# PKG900000001454.net
KiCad netlist of a schematic drawn in EAGLE
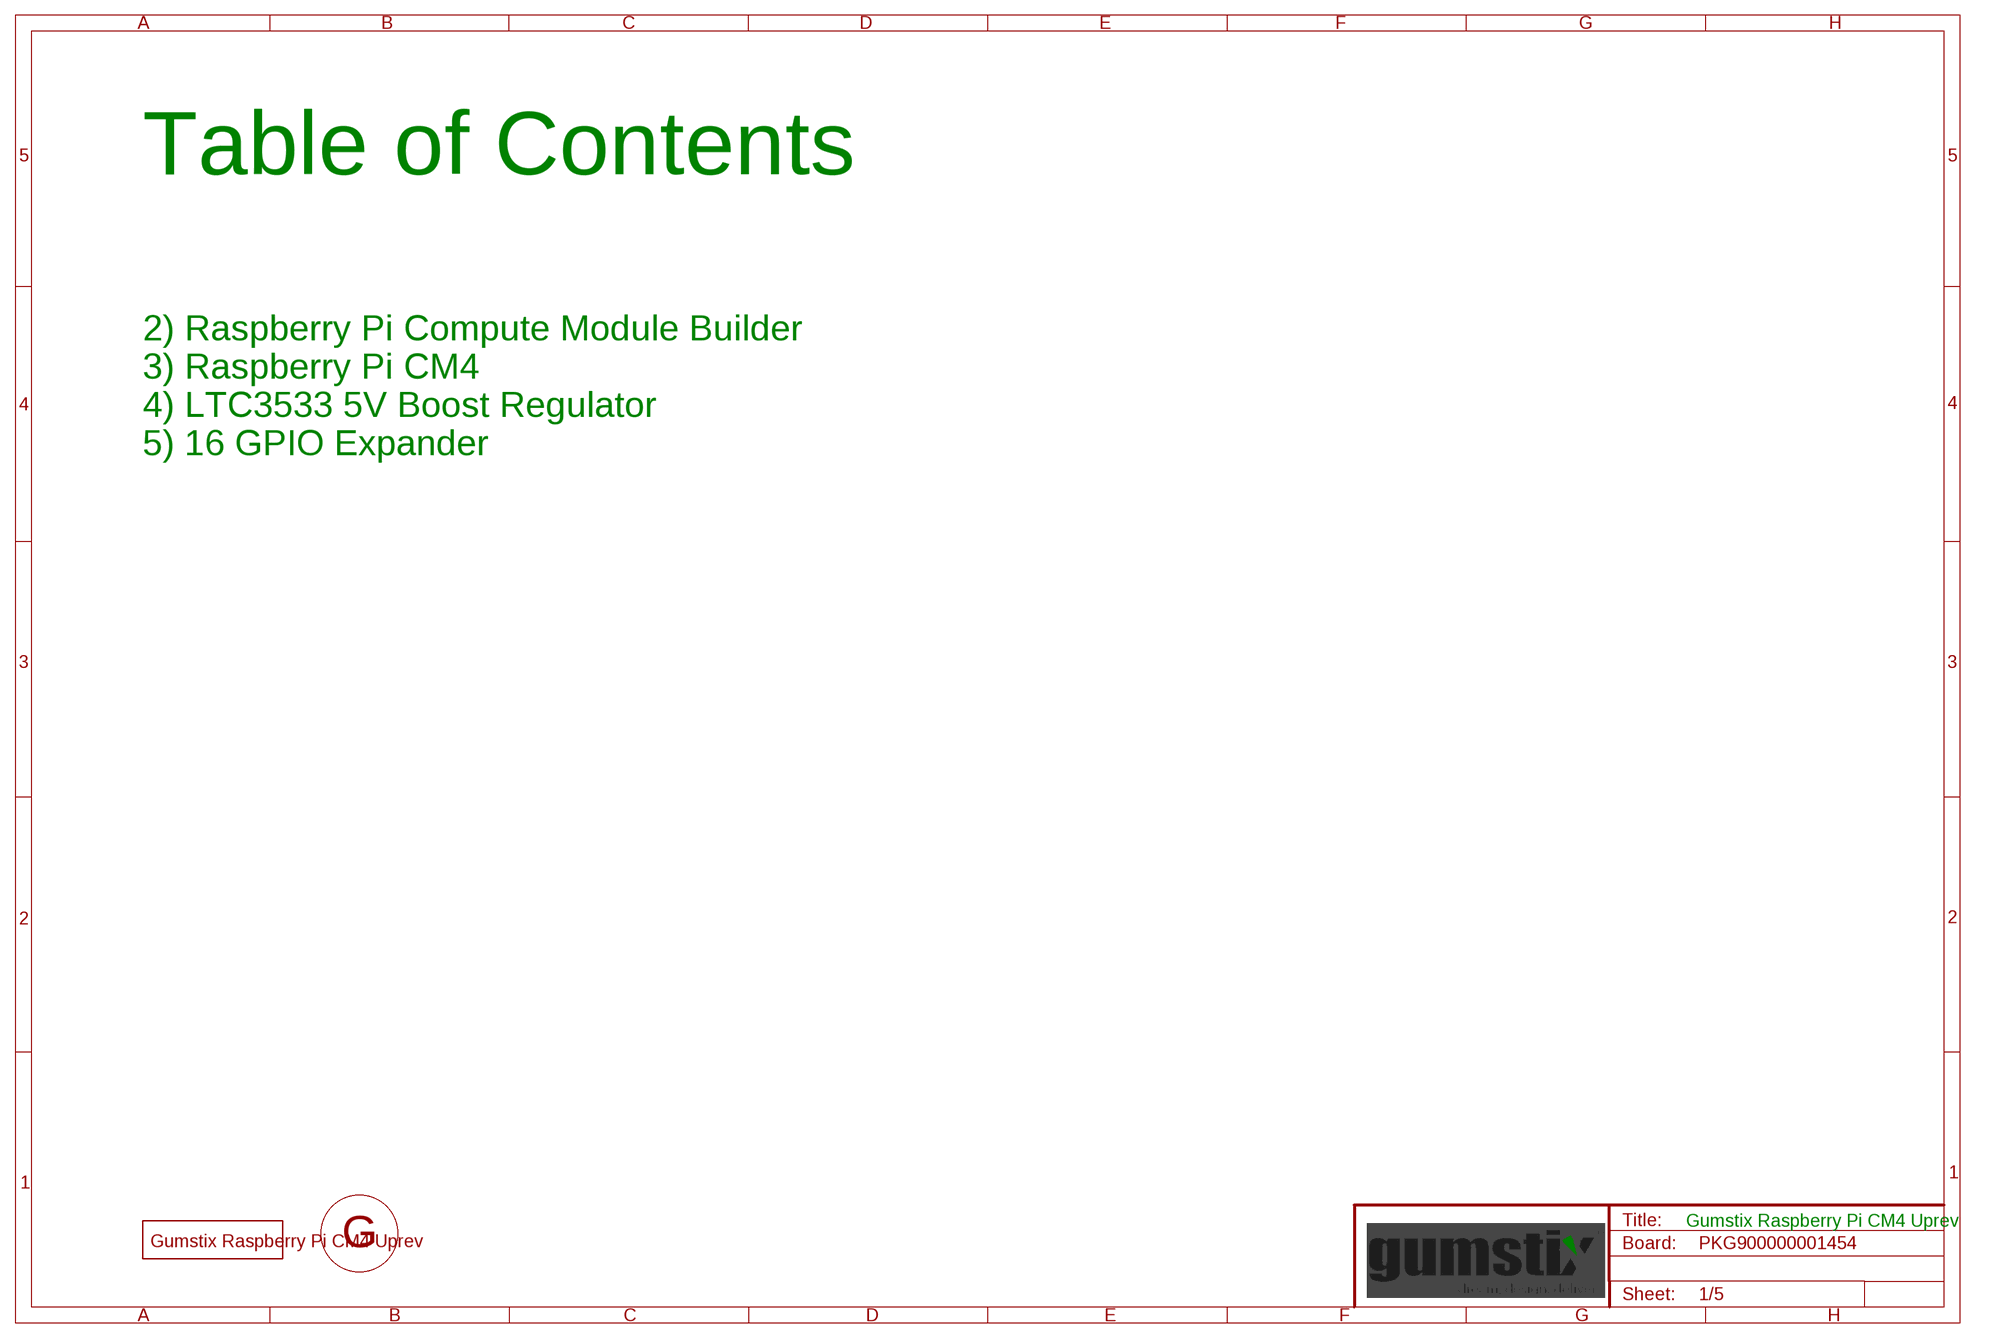
[diagram p0: schematic, sheet 1]
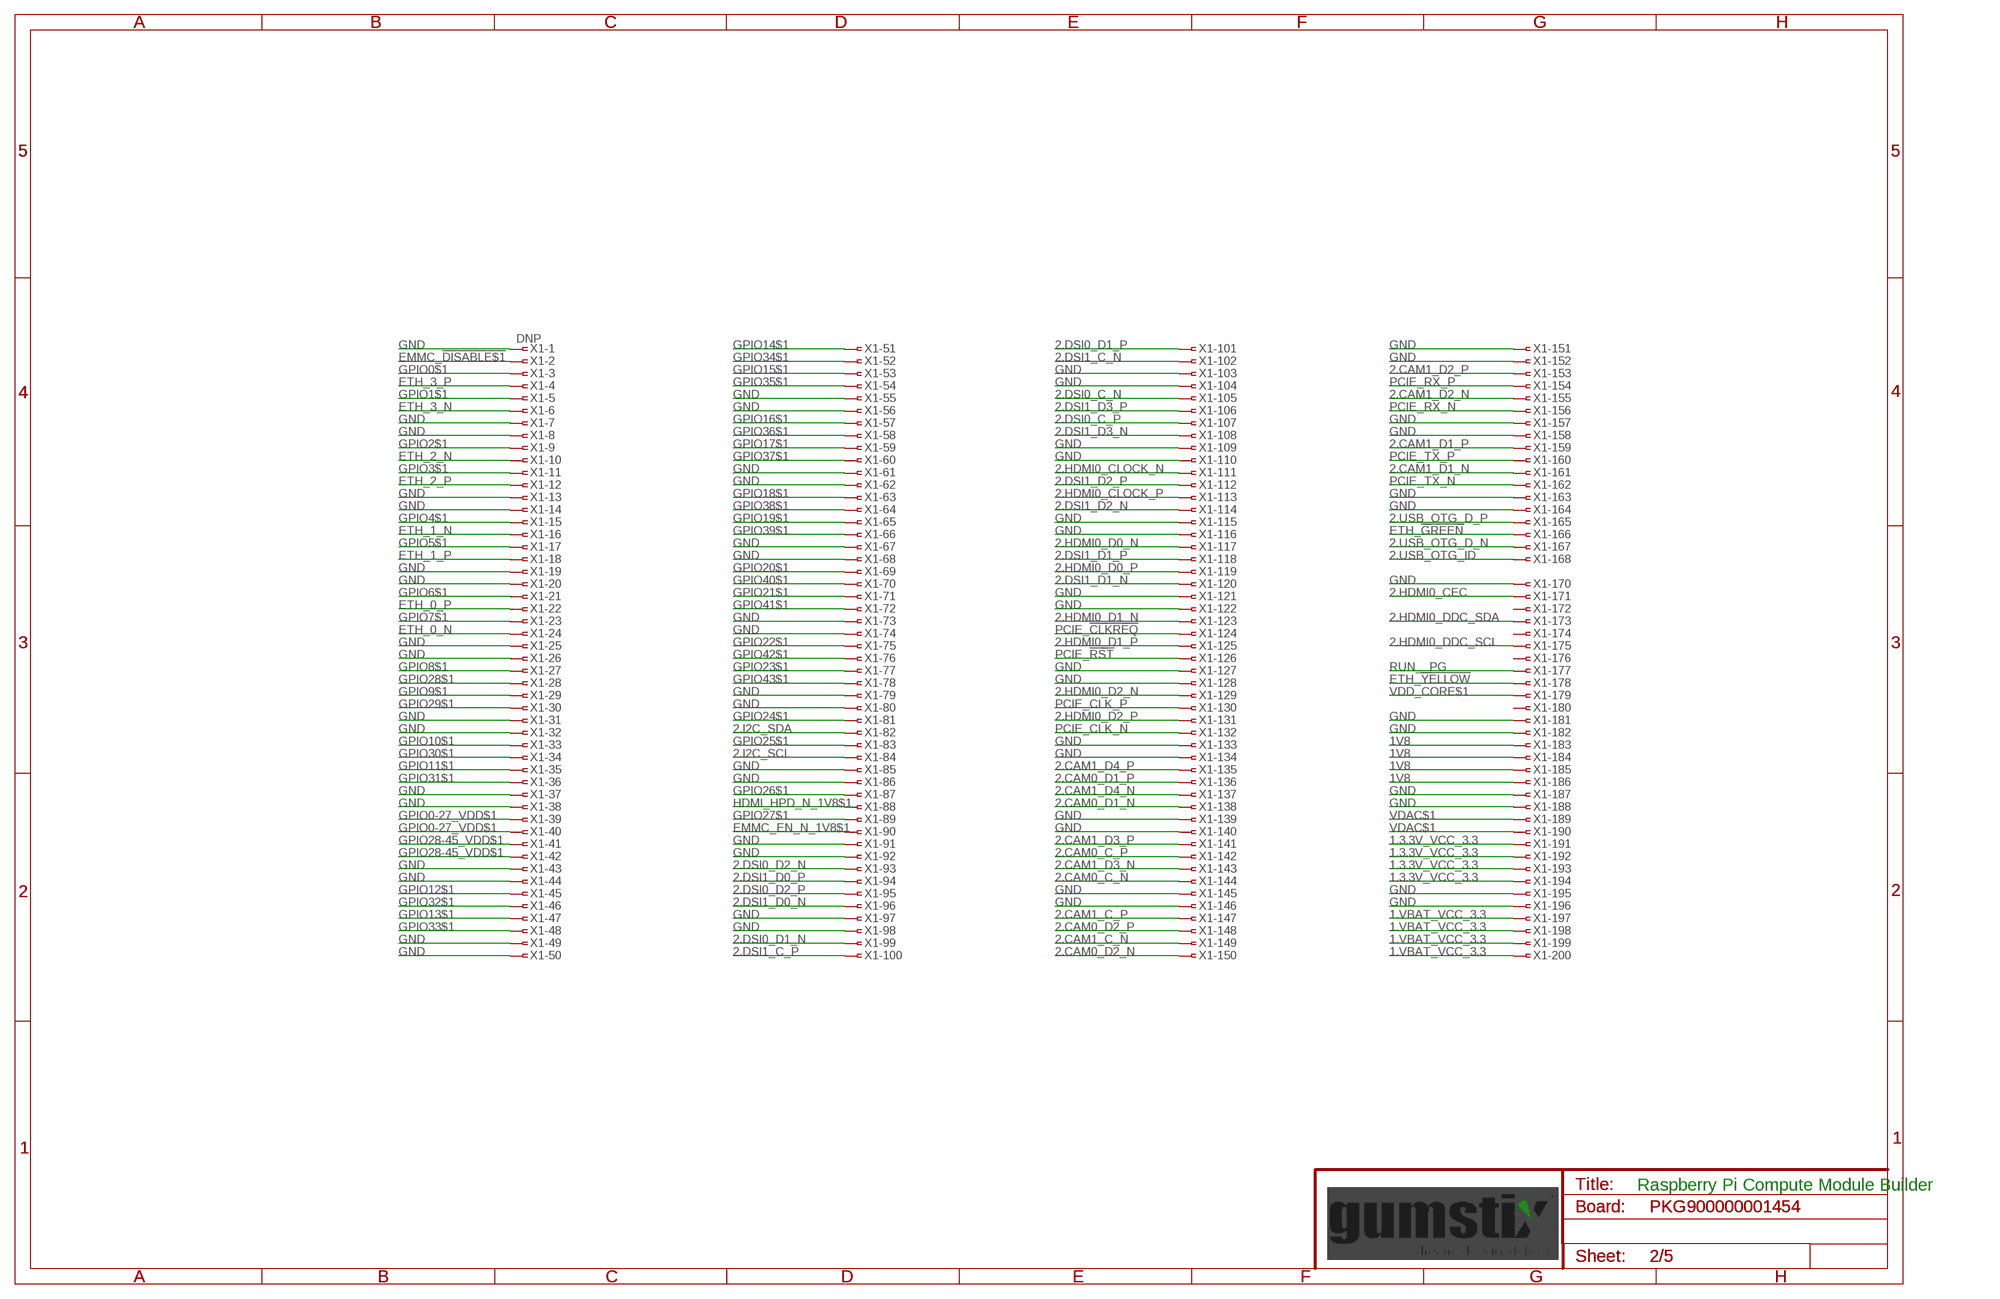
[diagram p1: schematic, sheet 2]
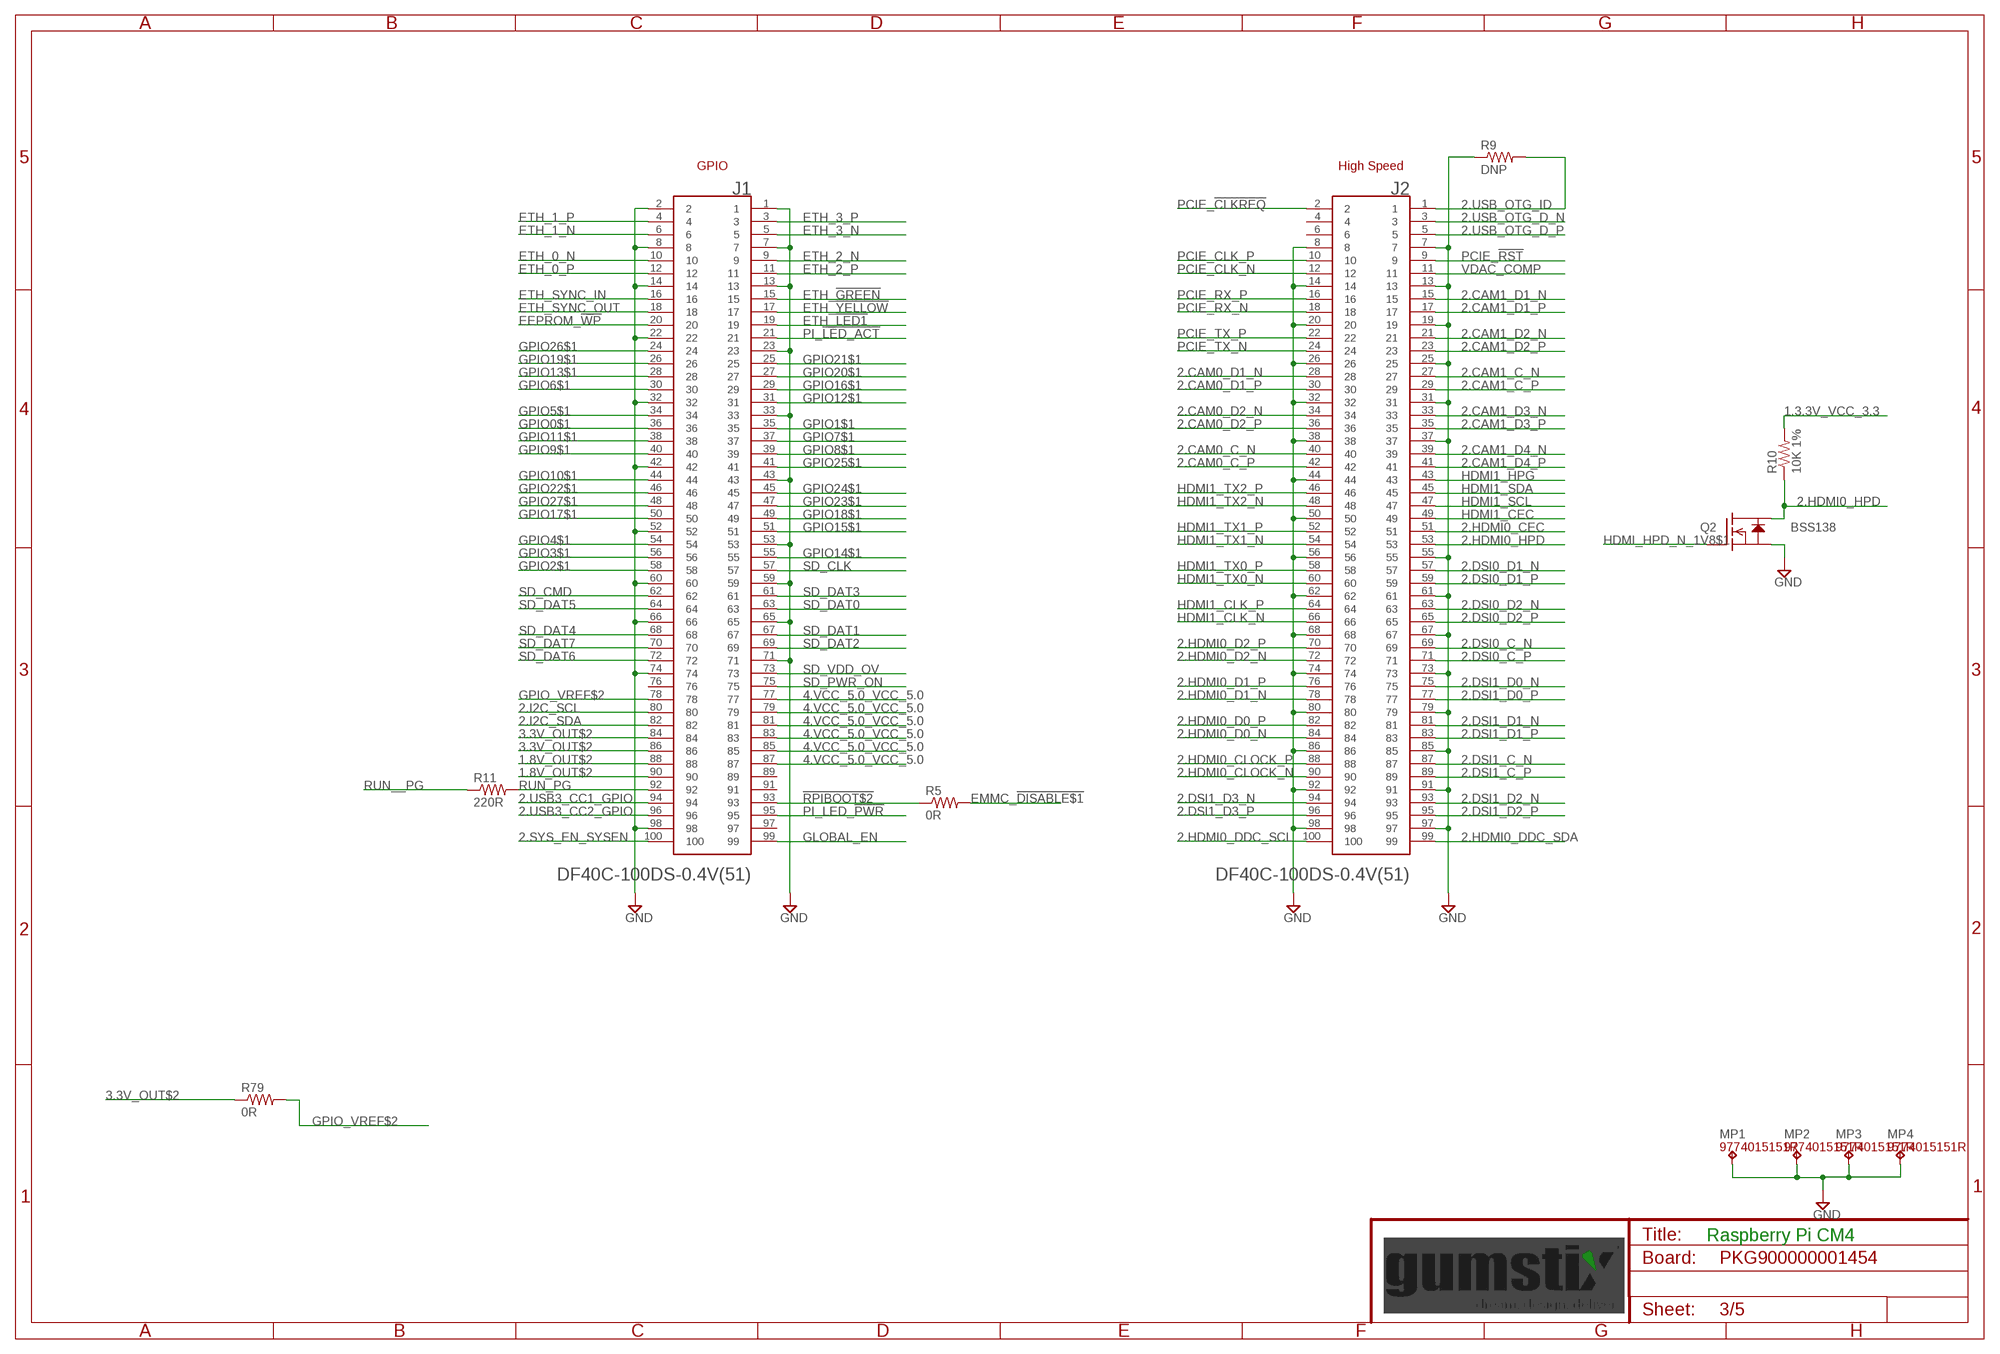
[diagram p2: schematic, sheet 3]
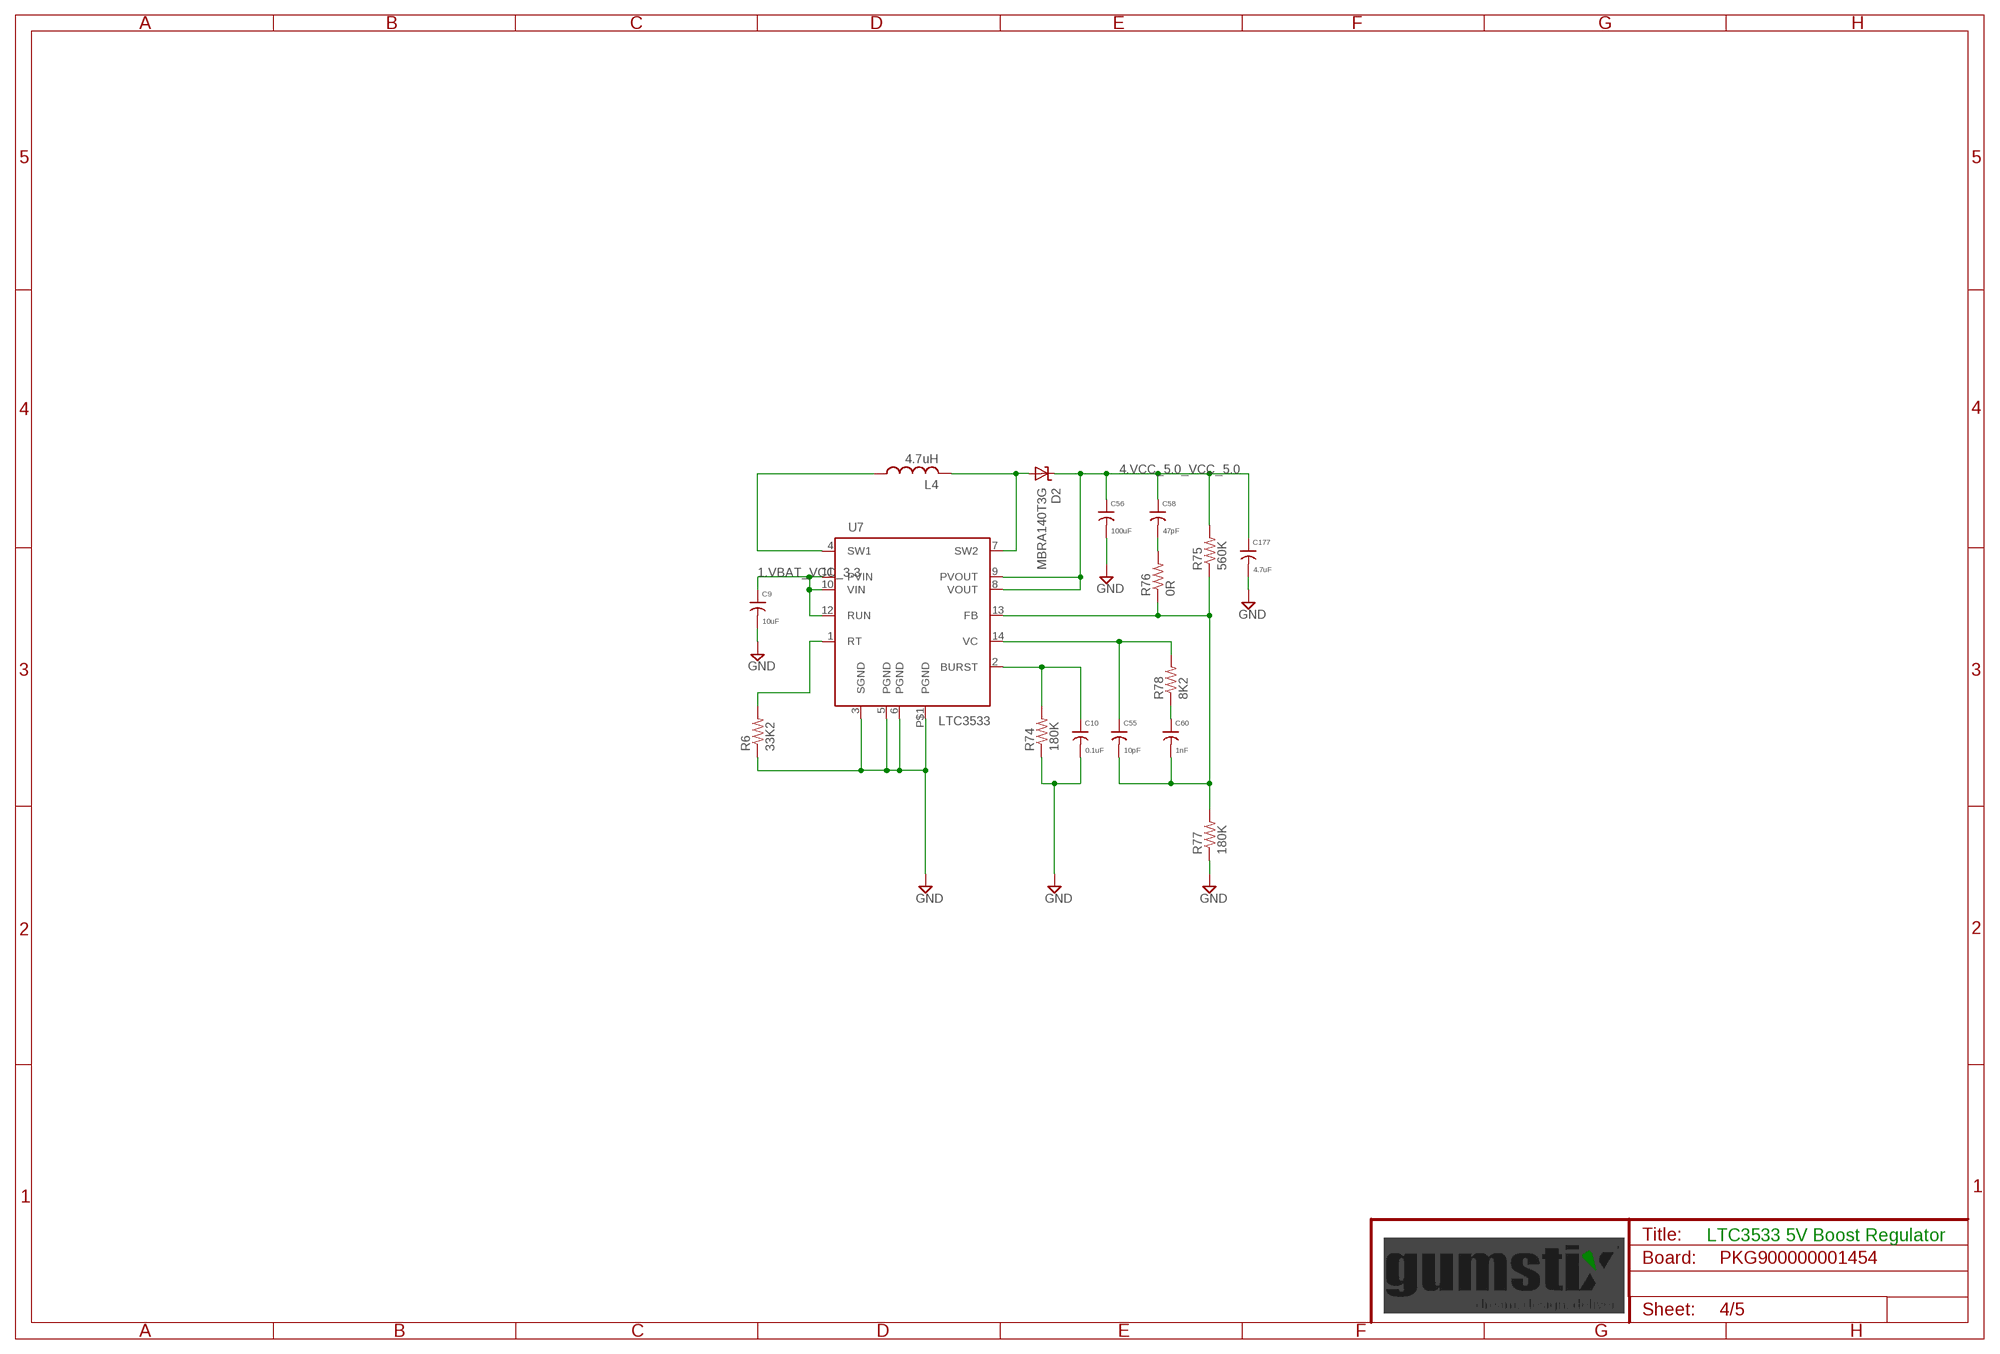
[diagram p3: schematic, sheet 4]
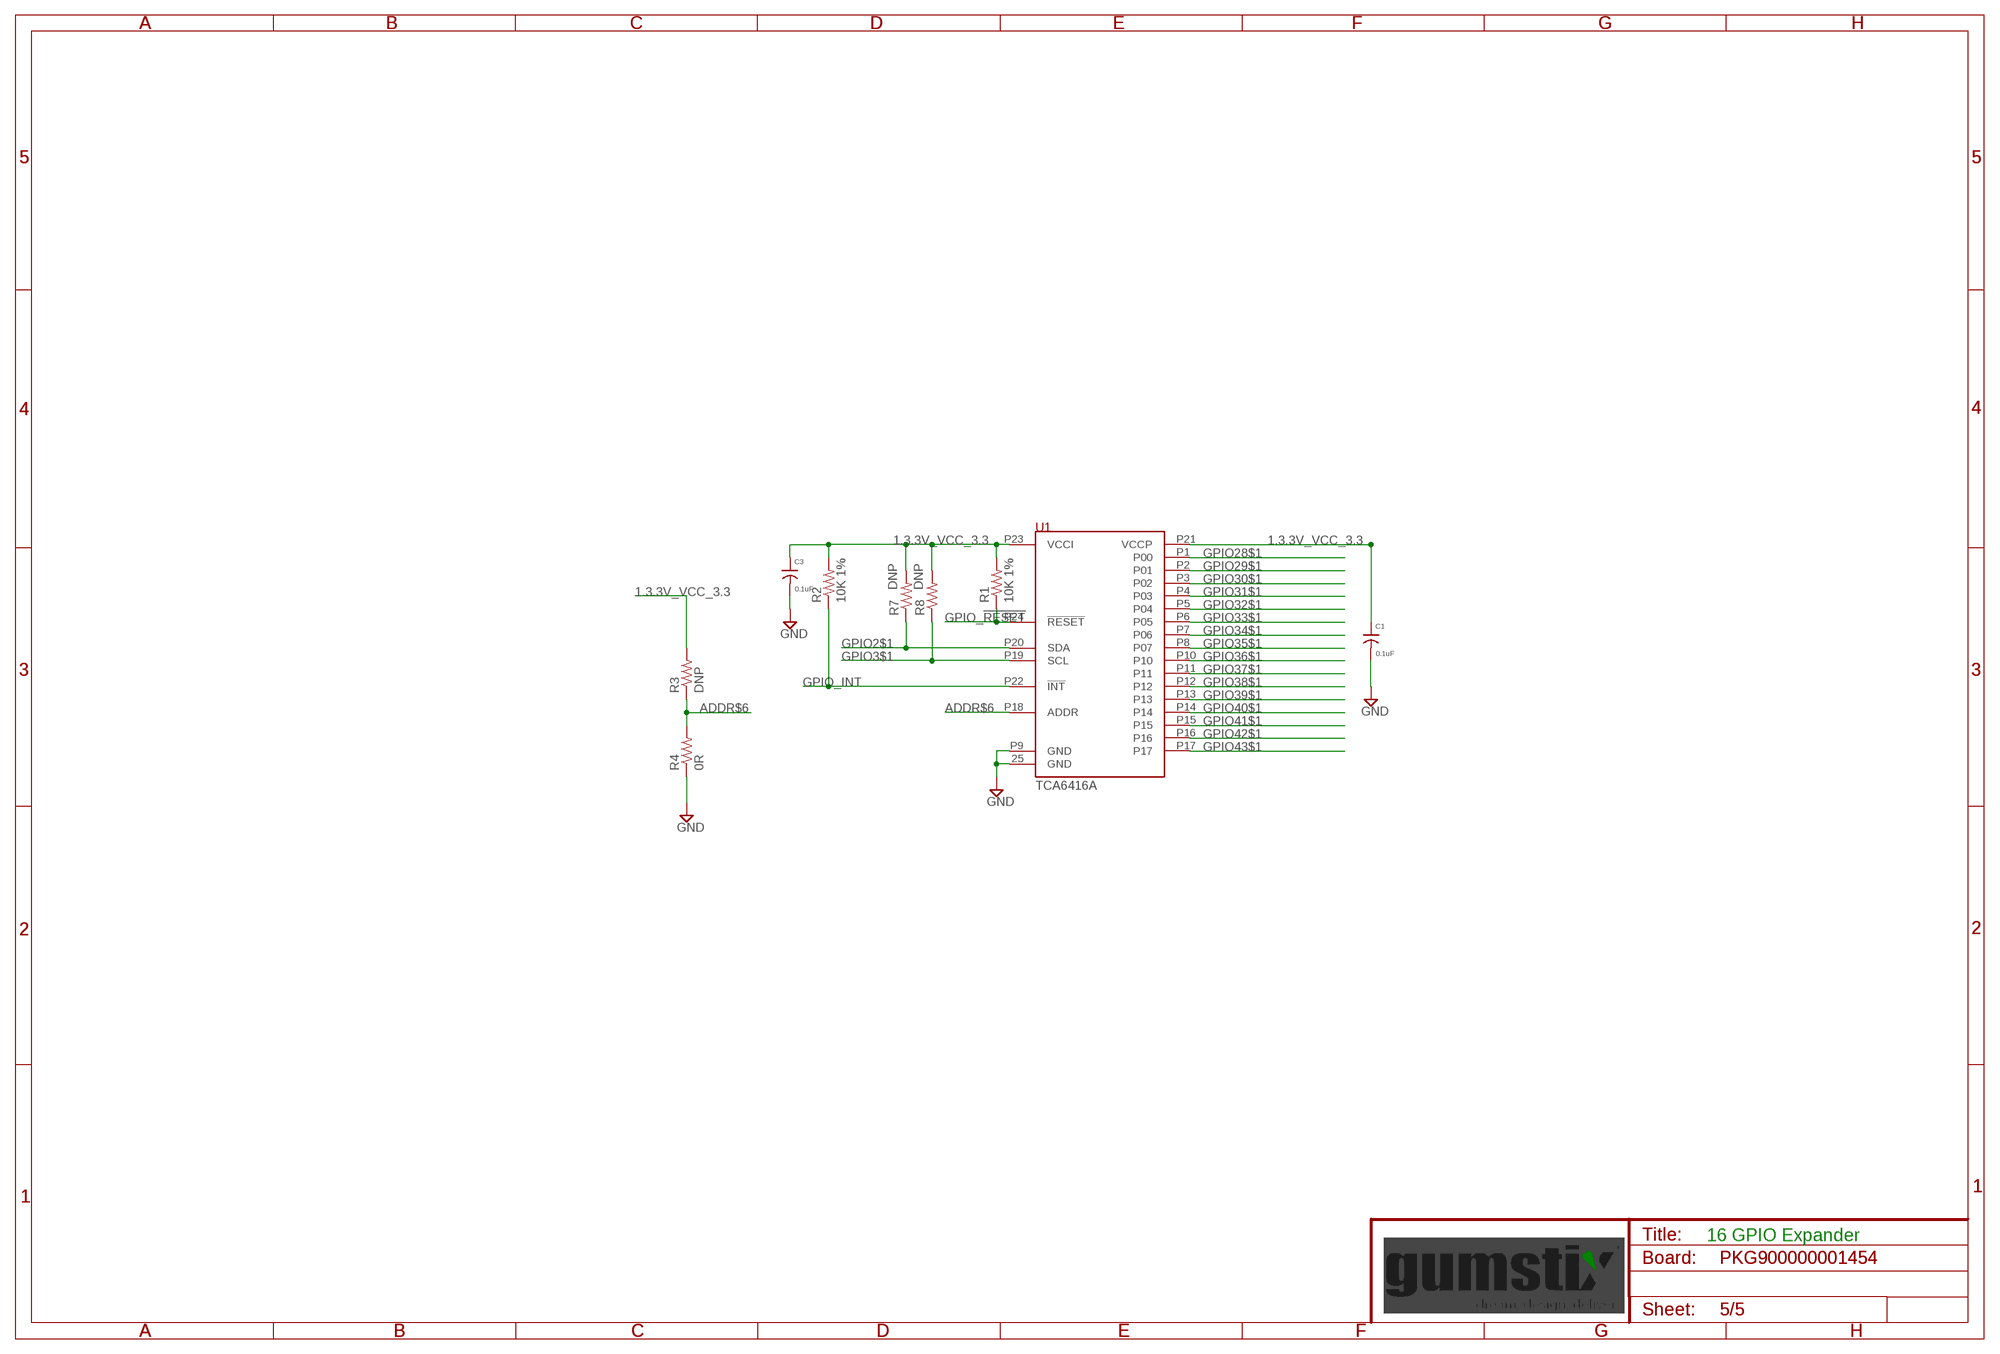
[diagram p4: schematic, sheet 5]

(export (version "E")
  (design (tool "Eeschema 10.0.6"))
  (components
    (comp (ref "X1")
      (value "DNP")
      (footprint "eagle-import:SLOT-1376408-1_1.8V_MOD")
      (libsource (lib "eagle-import") (part "1376408SLOT_1.8V_MOD"))
    )
    (comp (ref "C9")
      (value "10uF")
      (footprint "eagle-import:0603")
      (libsource (lib "eagle-import") (part "C0603"))
    )
    (comp (ref "C10")
      (value "0.1uF")
      (footprint "eagle-import:0201")
      (libsource (lib "eagle-import") (part "C0201"))
    )
    (comp (ref "C55")
      (value "10pF")
      (footprint "eagle-import:0201")
      (libsource (lib "eagle-import") (part "C0201"))
    )
    (comp (ref "C56")
      (value "100uF")
      (footprint "eagle-import:1206")
      (libsource (lib "eagle-import") (part "C1206"))
    )
    (comp (ref "C58")
      (value "47pF")
      (footprint "eagle-import:0201")
      (libsource (lib "eagle-import") (part "C0201"))
    )
    (comp (ref "C60")
      (value "1nF")
      (footprint "eagle-import:0402")
      (libsource (lib "eagle-import") (part "C0402"))
    )
    (comp (ref "C177")
      (value "4.7uF")
      (footprint "eagle-import:0603")
      (libsource (lib "eagle-import") (part "C0603"))
    )
    (comp (ref "D2")
      (value "MBRA140T3G")
      (footprint "eagle-import:SMAJ")
      (libsource (lib "eagle-import") (part "DSMA"))
    )
    (comp (ref "L4")
      (value "4.7uH")
      (footprint "eagle-import:B82462")
      (libsource (lib "eagle-import") (part "L82462"))
    )
    (comp (ref "R6")
      (value "33K2")
      (footprint "eagle-import:0402")
      (libsource (lib "eagle-import") (part "R0402"))
    )
    (comp (ref "R74")
      (value "180K")
      (footprint "eagle-import:0201")
      (libsource (lib "eagle-import") (part "R0201"))
    )
    (comp (ref "R75")
      (value "560K")
      (footprint "eagle-import:0402")
      (libsource (lib "eagle-import") (part "R0402"))
    )
    (comp (ref "R76")
      (value "0R")
      (footprint "eagle-import:0201")
      (libsource (lib "eagle-import") (part "R0201"))
    )
    (comp (ref "R77")
      (value "180K")
      (footprint "eagle-import:0201")
      (libsource (lib "eagle-import") (part "R0201"))
    )
    (comp (ref "R78")
      (value "8K2")
      (footprint "eagle-import:0402")
      (libsource (lib "eagle-import") (part "R0402"))
    )
    (comp (ref "U7")
      (value "LTC3533")
      (footprint "eagle-import:DFN-14")
      (libsource (lib "eagle-import") (part "LTC3533"))
    )
    (comp (ref "FD1")
      (value "DNP")
      (footprint "eagle-import:FIDUCIAL")
      (libsource (lib "eagle-import") (part "FIDUCIAL"))
    )
    (comp (ref "FD2")
      (value "DNP")
      (footprint "eagle-import:FIDUCIAL")
      (libsource (lib "eagle-import") (part "FIDUCIAL"))
    )
    (comp (ref "FD3")
      (value "DNP")
      (footprint "eagle-import:FIDUCIAL")
      (libsource (lib "eagle-import") (part "FIDUCIAL"))
    )
    (comp (ref "FD4")
      (value "DNP")
      (footprint "eagle-import:FIDUCIAL")
      (libsource (lib "eagle-import") (part "FIDUCIAL"))
    )
    (comp (ref "FD5")
      (value "DNP")
      (footprint "eagle-import:FIDUCIAL")
      (libsource (lib "eagle-import") (part "FIDUCIAL"))
    )
    (comp (ref "FD6")
      (value "DNP")
      (footprint "eagle-import:FIDUCIAL")
      (libsource (lib "eagle-import") (part "FIDUCIAL"))
    )
    (comp (ref "U$3")
      (value "DNP")
      (footprint "eagle-import:GEPPETTO_LABEL")
      (fields
        (field (name "BOARD") "PCB900000001454v2")
        (field (name "TITLE") "Gumstix Raspberry Pi CM4 Uprev")
        (field (name "YEAR") "2020")
      )
      (libsource (lib "eagle-import") (part "GEPPETTO_LABEL{dblquote}"))
    )
    (comp (ref "U$4")
      (value "DNP")
      (footprint "eagle-import:GEPPETTO_LOGO_SILK10")
      (libsource (lib "eagle-import") (part "GEPPETTO_LOGO10X10"))
    )
    (comp (ref "J1")
      (value "DF40C-100DS-0.4V(51)")
      (footprint "eagle-import:HRS_DF40C-100DS-0.4V(51)")
      (fields
        (field (name "DIGI-KEY_PART_NUMBER") "H11615CT-ND")
        (field (name "MF") "Hirose")
        (field (name "MP") "DF40C-100DS-0.4V_51_")
      )
      (libsource (lib "eagle-import") (part "DF40C-100DS-0.4V(51)"))
    )
    (comp (ref "J2")
      (value "DF40C-100DS-0.4V(51)")
      (footprint "eagle-import:HRS_DF40C-100DS-0.4V(51)")
      (fields
        (field (name "DIGI-KEY_PART_NUMBER") "H11615CT-ND")
        (field (name "MF") "Hirose")
        (field (name "MP") "DF40C-100DS-0.4V_51_")
      )
      (libsource (lib "eagle-import") (part "DF40C-100DS-0.4V(51)"))
    )
    (comp (ref "MP1")
      (value "9774015151R")
      (footprint "eagle-import:WA-SMSI_9774___151")
      (libsource (lib "eagle-import") (part "BULLET_CONN2.5MM"))
    )
    (comp (ref "MP2")
      (value "9774015151R")
      (footprint "eagle-import:WA-SMSI_9774___151")
      (libsource (lib "eagle-import") (part "BULLET_CONN2.5MM"))
    )
    (comp (ref "MP3")
      (value "9774015151R")
      (footprint "eagle-import:WA-SMSI_9774___151")
      (libsource (lib "eagle-import") (part "BULLET_CONN2.5MM"))
    )
    (comp (ref "MP4")
      (value "9774015151R")
      (footprint "eagle-import:WA-SMSI_9774___151")
      (libsource (lib "eagle-import") (part "BULLET_CONN2.5MM"))
    )
    (comp (ref "Q2")
      (value "BSS138")
      (footprint "eagle-import:SOT23")
      (libsource (lib "eagle-import") (part "BSS138"))
    )
    (comp (ref "R5")
      (value "0R")
      (footprint "eagle-import:0201")
      (libsource (lib "eagle-import") (part "R0201"))
    )
    (comp (ref "R9")
      (value "DNP")
      (footprint "eagle-import:0201")
      (libsource (lib "eagle-import") (part "R0201"))
    )
    (comp (ref "R10")
      (value "10K 1%")
      (footprint "eagle-import:0201")
      (libsource (lib "eagle-import") (part "R0201"))
    )
    (comp (ref "R11")
      (value "220R")
      (footprint "eagle-import:0402")
      (libsource (lib "eagle-import") (part "R0402"))
    )
    (comp (ref "R79")
      (value "0R")
      (footprint "eagle-import:0201")
      (libsource (lib "eagle-import") (part "R0201"))
    )
    (comp (ref "C1")
      (value "0.1uF")
      (footprint "eagle-import:0201")
      (libsource (lib "eagle-import") (part "C0201"))
    )
    (comp (ref "C3")
      (value "0.1uF")
      (footprint "eagle-import:0201")
      (libsource (lib "eagle-import") (part "C0201"))
    )
    (comp (ref "R1")
      (value "10K 1%")
      (footprint "eagle-import:0201")
      (libsource (lib "eagle-import") (part "R0201"))
    )
    (comp (ref "R2")
      (value "10K 1%")
      (footprint "eagle-import:0201")
      (libsource (lib "eagle-import") (part "R0201"))
    )
    (comp (ref "R3")
      (value "DNP")
      (footprint "eagle-import:0201")
      (libsource (lib "eagle-import") (part "R0201"))
    )
    (comp (ref "R4")
      (value "0R")
      (footprint "eagle-import:0201")
      (libsource (lib "eagle-import") (part "R0201"))
    )
    (comp (ref "R7")
      (value "DNP")
      (footprint "eagle-import:0201")
      (libsource (lib "eagle-import") (part "R0201"))
    )
    (comp (ref "R8")
      (value "DNP")
      (footprint "eagle-import:0201")
      (libsource (lib "eagle-import") (part "R0201"))
    )
    (comp (ref "U1")
      (value "TCA6416A")
      (footprint "eagle-import:WQFN24")
      (libsource (lib "eagle-import") (part "TCA6416A"))
    )
  )
  (nets
    (net (code "1") (name "1.3.3V_VCC_3.3") (class "Default")
      (node (ref "C1") (pin "1") (pinfunction "1_1") (pintype "passive"))
      (node (ref "C3") (pin "1") (pinfunction "1_1") (pintype "passive"))
      (node (ref "R1") (pin "2") (pinfunction "2_2") (pintype "passive"))
      (node (ref "R10") (pin "2") (pinfunction "2_2") (pintype "passive"))
      (node (ref "R2") (pin "2") (pinfunction "2_2") (pintype "passive"))
      (node (ref "R3") (pin "2") (pinfunction "2_2") (pintype "passive"))
      (node (ref "R7") (pin "2") (pinfunction "2_2") (pintype "passive"))
      (node (ref "R8") (pin "2") (pinfunction "2_2") (pintype "passive"))
      (node (ref "U1") (pin "P21") (pinfunction "VCCP_P21") (pintype "power_in"))
      (node (ref "U1") (pin "P23") (pinfunction "VCCI_P23") (pintype "power_in"))
      (node (ref "X1") (pin "191") (pinfunction "1_191") (pintype "passive"))
      (node (ref "X1") (pin "192") (pinfunction "1_192") (pintype "passive"))
      (node (ref "X1") (pin "193") (pinfunction "1_193") (pintype "passive"))
      (node (ref "X1") (pin "194") (pinfunction "1_194") (pintype "passive"))
    )
    (net (code "2") (name "1.8V_OUT$2") (class "Default")
      (node (ref "J1") (pin "88") (pinfunction "88_88") (pintype "passive"))
      (node (ref "J1") (pin "90") (pinfunction "90_90") (pintype "passive"))
    )
    (net (code "3") (name "1.VBAT_VCC_3.3") (class "Default")
      (node (ref "C9") (pin "1") (pinfunction "1_1") (pintype "passive"))
      (node (ref "U7") (pin "10") (pinfunction "VIN_10") (pintype "power_in"))
      (node (ref "U7") (pin "11") (pinfunction "PVIN_11") (pintype "power_in"))
      (node (ref "U7") (pin "12") (pinfunction "RUN_12") (pintype "input"))
      (node (ref "X1") (pin "197") (pinfunction "1_197") (pintype "passive"))
      (node (ref "X1") (pin "198") (pinfunction "1_198") (pintype "passive"))
      (node (ref "X1") (pin "199") (pinfunction "1_199") (pintype "passive"))
      (node (ref "X1") (pin "200") (pinfunction "1_200") (pintype "passive"))
    )
    (net (code "4") (name "1V8") (class "Default")
      (node (ref "X1") (pin "183") (pinfunction "1_183") (pintype "passive"))
      (node (ref "X1") (pin "184") (pinfunction "1_184") (pintype "passive"))
      (node (ref "X1") (pin "185") (pinfunction "1_185") (pintype "passive"))
      (node (ref "X1") (pin "186") (pinfunction "1_186") (pintype "passive"))
    )
    (net (code "5") (name "2.CAM0_C_N") (class "Default")
      (node (ref "J2") (pin "40") (pinfunction "40_40") (pintype "passive"))
      (node (ref "X1") (pin "144") (pinfunction "1_144") (pintype "passive"))
    )
    (net (code "6") (name "2.CAM0_C_P") (class "Default")
      (node (ref "J2") (pin "42") (pinfunction "42_42") (pintype "passive"))
      (node (ref "X1") (pin "142") (pinfunction "1_142") (pintype "passive"))
    )
    (net (code "7") (name "2.CAM0_D1_N") (class "Default")
      (node (ref "J2") (pin "28") (pinfunction "28_28") (pintype "passive"))
      (node (ref "X1") (pin "138") (pinfunction "1_138") (pintype "passive"))
    )
    (net (code "8") (name "2.CAM0_D1_P") (class "Default")
      (node (ref "J2") (pin "30") (pinfunction "30_30") (pintype "passive"))
      (node (ref "X1") (pin "136") (pinfunction "1_136") (pintype "passive"))
    )
    (net (code "9") (name "2.CAM0_D2_N") (class "Default")
      (node (ref "J2") (pin "34") (pinfunction "34_34") (pintype "passive"))
      (node (ref "X1") (pin "150") (pinfunction "1_150") (pintype "passive"))
    )
    (net (code "10") (name "2.CAM0_D2_P") (class "Default")
      (node (ref "J2") (pin "36") (pinfunction "36_36") (pintype "passive"))
      (node (ref "X1") (pin "148") (pinfunction "1_148") (pintype "passive"))
    )
    (net (code "11") (name "2.CAM1_C_N") (class "Default")
      (node (ref "J2") (pin "27") (pinfunction "27_27") (pintype "passive"))
      (node (ref "X1") (pin "149") (pinfunction "1_149") (pintype "passive"))
    )
    (net (code "12") (name "2.CAM1_C_P") (class "Default")
      (node (ref "J2") (pin "29") (pinfunction "29_29") (pintype "passive"))
      (node (ref "X1") (pin "147") (pinfunction "1_147") (pintype "passive"))
    )
    (net (code "13") (name "2.CAM1_D1_N") (class "Default")
      (node (ref "J2") (pin "15") (pinfunction "15_15") (pintype "passive"))
      (node (ref "X1") (pin "161") (pinfunction "1_161") (pintype "passive"))
    )
    (net (code "14") (name "2.CAM1_D1_P") (class "Default")
      (node (ref "J2") (pin "17") (pinfunction "17_17") (pintype "passive"))
      (node (ref "X1") (pin "159") (pinfunction "1_159") (pintype "passive"))
    )
    (net (code "15") (name "2.CAM1_D2_N") (class "Default")
      (node (ref "J2") (pin "21") (pinfunction "21_21") (pintype "passive"))
      (node (ref "X1") (pin "155") (pinfunction "1_155") (pintype "passive"))
    )
    (net (code "16") (name "2.CAM1_D2_P") (class "Default")
      (node (ref "J2") (pin "23") (pinfunction "23_23") (pintype "passive"))
      (node (ref "X1") (pin "153") (pinfunction "1_153") (pintype "passive"))
    )
    (net (code "17") (name "2.CAM1_D3_N") (class "Default")
      (node (ref "J2") (pin "33") (pinfunction "33_33") (pintype "passive"))
      (node (ref "X1") (pin "143") (pinfunction "1_143") (pintype "passive"))
    )
    (net (code "18") (name "2.CAM1_D3_P") (class "Default")
      (node (ref "J2") (pin "35") (pinfunction "35_35") (pintype "passive"))
      (node (ref "X1") (pin "141") (pinfunction "1_141") (pintype "passive"))
    )
    (net (code "19") (name "2.CAM1_D4_N") (class "Default")
      (node (ref "J2") (pin "39") (pinfunction "39_39") (pintype "passive"))
      (node (ref "X1") (pin "137") (pinfunction "1_137") (pintype "passive"))
    )
    (net (code "20") (name "2.CAM1_D4_P") (class "Default")
      (node (ref "J2") (pin "41") (pinfunction "41_41") (pintype "passive"))
      (node (ref "X1") (pin "135") (pinfunction "1_135") (pintype "passive"))
    )
    (net (code "21") (name "2.DSI0_C_N") (class "Default")
      (node (ref "J2") (pin "69") (pinfunction "69_69") (pintype "passive"))
      (node (ref "X1") (pin "105") (pinfunction "1_105") (pintype "passive"))
    )
    (net (code "22") (name "2.DSI0_C_P") (class "Default")
      (node (ref "J2") (pin "71") (pinfunction "71_71") (pintype "passive"))
      (node (ref "X1") (pin "107") (pinfunction "1_107") (pintype "passive"))
    )
    (net (code "23") (name "2.DSI0_D1_N") (class "Default")
      (node (ref "J2") (pin "57") (pinfunction "57_57") (pintype "passive"))
      (node (ref "X1") (pin "99") (pinfunction "1_99") (pintype "passive"))
    )
    (net (code "24") (name "2.DSI0_D1_P") (class "Default")
      (node (ref "J2") (pin "59") (pinfunction "59_59") (pintype "passive"))
      (node (ref "X1") (pin "101") (pinfunction "1_101") (pintype "passive"))
    )
    (net (code "25") (name "2.DSI0_D2_N") (class "Default")
      (node (ref "J2") (pin "63") (pinfunction "63_63") (pintype "passive"))
      (node (ref "X1") (pin "93") (pinfunction "1_93") (pintype "passive"))
    )
    (net (code "26") (name "2.DSI0_D2_P") (class "Default")
      (node (ref "J2") (pin "65") (pinfunction "65_65") (pintype "passive"))
      (node (ref "X1") (pin "95") (pinfunction "1_95") (pintype "passive"))
    )
    (net (code "27") (name "2.DSI1_C_N") (class "Default")
      (node (ref "J2") (pin "87") (pinfunction "87_87") (pintype "passive"))
      (node (ref "X1") (pin "102") (pinfunction "1_102") (pintype "passive"))
    )
    (net (code "28") (name "2.DSI1_C_P") (class "Default")
      (node (ref "J2") (pin "89") (pinfunction "89_89") (pintype "passive"))
      (node (ref "X1") (pin "100") (pinfunction "1_100") (pintype "passive"))
    )
    (net (code "29") (name "2.DSI1_D0_N") (class "Default")
      (node (ref "J2") (pin "75") (pinfunction "75_75") (pintype "passive"))
      (node (ref "X1") (pin "96") (pinfunction "1_96") (pintype "passive"))
    )
    (net (code "30") (name "2.DSI1_D0_P") (class "Default")
      (node (ref "J2") (pin "77") (pinfunction "77_77") (pintype "passive"))
      (node (ref "X1") (pin "94") (pinfunction "1_94") (pintype "passive"))
    )
    (net (code "31") (name "2.DSI1_D1_N") (class "Default")
      (node (ref "J2") (pin "81") (pinfunction "81_81") (pintype "passive"))
      (node (ref "X1") (pin "120") (pinfunction "1_120") (pintype "passive"))
    )
    (net (code "32") (name "2.DSI1_D1_P") (class "Default")
      (node (ref "J2") (pin "83") (pinfunction "83_83") (pintype "passive"))
      (node (ref "X1") (pin "118") (pinfunction "1_118") (pintype "passive"))
    )
    (net (code "33") (name "2.DSI1_D2_N") (class "Default")
      (node (ref "J2") (pin "93") (pinfunction "93_93") (pintype "passive"))
      (node (ref "X1") (pin "114") (pinfunction "1_114") (pintype "passive"))
    )
    (net (code "34") (name "2.DSI1_D2_P") (class "Default")
      (node (ref "J2") (pin "95") (pinfunction "95_95") (pintype "passive"))
      (node (ref "X1") (pin "112") (pinfunction "1_112") (pintype "passive"))
    )
    (net (code "35") (name "2.DSI1_D3_N") (class "Default")
      (node (ref "J2") (pin "94") (pinfunction "94_94") (pintype "passive"))
      (node (ref "X1") (pin "108") (pinfunction "1_108") (pintype "passive"))
    )
    (net (code "36") (name "2.DSI1_D3_P") (class "Default")
      (node (ref "J2") (pin "96") (pinfunction "96_96") (pintype "passive"))
      (node (ref "X1") (pin "106") (pinfunction "1_106") (pintype "passive"))
    )
    (net (code "37") (name "2.HDMI0_CEC") (class "Default")
      (node (ref "J2") (pin "51") (pinfunction "51_51") (pintype "passive"))
      (node (ref "X1") (pin "171") (pinfunction "1_171") (pintype "passive"))
    )
    (net (code "38") (name "2.HDMI0_CLOCK_N") (class "Default")
      (node (ref "J2") (pin "90") (pinfunction "90_90") (pintype "passive"))
      (node (ref "X1") (pin "111") (pinfunction "1_111") (pintype "passive"))
    )
    (net (code "39") (name "2.HDMI0_CLOCK_P") (class "Default")
      (node (ref "J2") (pin "88") (pinfunction "88_88") (pintype "passive"))
      (node (ref "X1") (pin "113") (pinfunction "1_113") (pintype "passive"))
    )
    (net (code "40") (name "2.HDMI0_D0_N") (class "Default")
      (node (ref "J2") (pin "84") (pinfunction "84_84") (pintype "passive"))
      (node (ref "X1") (pin "117") (pinfunction "1_117") (pintype "passive"))
    )
    (net (code "41") (name "2.HDMI0_D0_P") (class "Default")
      (node (ref "J2") (pin "82") (pinfunction "82_82") (pintype "passive"))
      (node (ref "X1") (pin "119") (pinfunction "1_119") (pintype "passive"))
    )
    (net (code "42") (name "2.HDMI0_D1_N") (class "Default")
      (node (ref "J2") (pin "78") (pinfunction "78_78") (pintype "passive"))
      (node (ref "X1") (pin "123") (pinfunction "1_123") (pintype "passive"))
    )
    (net (code "43") (name "2.HDMI0_D1_P") (class "Default")
      (node (ref "J2") (pin "76") (pinfunction "76_76") (pintype "passive"))
      (node (ref "X1") (pin "125") (pinfunction "1_125") (pintype "passive"))
    )
    (net (code "44") (name "2.HDMI0_D2_N") (class "Default")
      (node (ref "J2") (pin "72") (pinfunction "72_72") (pintype "passive"))
      (node (ref "X1") (pin "129") (pinfunction "1_129") (pintype "passive"))
    )
    (net (code "45") (name "2.HDMI0_D2_P") (class "Default")
      (node (ref "J2") (pin "70") (pinfunction "70_70") (pintype "passive"))
      (node (ref "X1") (pin "131") (pinfunction "1_131") (pintype "passive"))
    )
    (net (code "46") (name "2.HDMI0_DDC_SCL") (class "Default")
      (node (ref "J2") (pin "100") (pinfunction "100_100") (pintype "passive"))
      (node (ref "X1") (pin "175") (pinfunction "1_175") (pintype "passive"))
    )
    (net (code "47") (name "2.HDMI0_DDC_SDA") (class "Default")
      (node (ref "J2") (pin "99") (pinfunction "99_99") (pintype "passive"))
      (node (ref "X1") (pin "173") (pinfunction "1_173") (pintype "passive"))
    )
    (net (code "48") (name "2.HDMI0_HPD") (class "Default")
      (node (ref "J2") (pin "53") (pinfunction "53_53") (pintype "passive"))
      (node (ref "Q2") (pin "3") (pinfunction "D_3") (pintype "passive"))
      (node (ref "R10") (pin "1") (pinfunction "1_1") (pintype "passive"))
    )
    (net (code "49") (name "2.I2C_SCL") (class "Default")
      (node (ref "J1") (pin "80") (pinfunction "80_80") (pintype "passive"))
      (node (ref "X1") (pin "84") (pinfunction "1_84") (pintype "passive"))
    )
    (net (code "50") (name "2.I2C_SDA") (class "Default")
      (node (ref "J1") (pin "82") (pinfunction "82_82") (pintype "passive"))
      (node (ref "X1") (pin "82") (pinfunction "1_82") (pintype "passive"))
    )
    (net (code "51") (name "2.SYS_EN_SYSEN") (class "Default")
      (node (ref "J1") (pin "100") (pinfunction "100_100") (pintype "passive"))
    )
    (net (code "52") (name "2.USB3_CC1_GPIO") (class "Default")
      (node (ref "J1") (pin "94") (pinfunction "94_94") (pintype "passive"))
    )
    (net (code "53") (name "2.USB3_CC2_GPIO") (class "Default")
      (node (ref "J1") (pin "96") (pinfunction "96_96") (pintype "passive"))
    )
    (net (code "54") (name "2.USB_OTG_D_N") (class "Default")
      (node (ref "J2") (pin "3") (pinfunction "3_3") (pintype "passive"))
      (node (ref "X1") (pin "167") (pinfunction "1_167") (pintype "passive"))
    )
    (net (code "55") (name "2.USB_OTG_D_P") (class "Default")
      (node (ref "J2") (pin "5") (pinfunction "5_5") (pintype "passive"))
      (node (ref "X1") (pin "165") (pinfunction "1_165") (pintype "passive"))
    )
    (net (code "56") (name "2.USB_OTG_ID") (class "Default")
      (node (ref "J2") (pin "1") (pinfunction "1_1") (pintype "passive"))
      (node (ref "R9") (pin "2") (pinfunction "2_2") (pintype "passive"))
      (node (ref "X1") (pin "168") (pinfunction "1_168") (pintype "passive"))
    )
    (net (code "57") (name "3.3V_OUT$2") (class "Default")
      (node (ref "J1") (pin "84") (pinfunction "84_84") (pintype "passive"))
      (node (ref "J1") (pin "86") (pinfunction "86_86") (pintype "passive"))
      (node (ref "R79") (pin "1") (pinfunction "1_1") (pintype "passive"))
    )
    (net (code "58") (name "4.VCC_5.0_VCC_5.0") (class "Default")
      (node (ref "C177") (pin "1") (pinfunction "1_1") (pintype "passive"))
      (node (ref "C56") (pin "1") (pinfunction "1_1") (pintype "passive"))
      (node (ref "C58") (pin "1") (pinfunction "1_1") (pintype "passive"))
      (node (ref "D2") (pin "C") (pinfunction "C_C") (pintype "passive"))
      (node (ref "J1") (pin "77") (pinfunction "77_77") (pintype "passive"))
      (node (ref "J1") (pin "79") (pinfunction "79_79") (pintype "passive"))
      (node (ref "J1") (pin "81") (pinfunction "81_81") (pintype "passive"))
      (node (ref "J1") (pin "83") (pinfunction "83_83") (pintype "passive"))
      (node (ref "J1") (pin "85") (pinfunction "85_85") (pintype "passive"))
      (node (ref "J1") (pin "87") (pinfunction "87_87") (pintype "passive"))
      (node (ref "R75") (pin "2") (pinfunction "2_2") (pintype "passive"))
      (node (ref "U7") (pin "8") (pinfunction "VOUT_8") (pintype "input"))
      (node (ref "U7") (pin "9") (pinfunction "PVOUT_9") (pintype "output"))
    )
    (net (code "59") (name "ADDR$6") (class "Default")
      (node (ref "R3") (pin "1") (pinfunction "1_1") (pintype "passive"))
      (node (ref "R4") (pin "2") (pinfunction "2_2") (pintype "passive"))
      (node (ref "U1") (pin "P18") (pinfunction "ADDR_P18") (pintype "bidirectional"))
    )
    (net (code "60") (name "EEPROM_~{WP}") (class "Default")
      (node (ref "J1") (pin "20") (pinfunction "20_20") (pintype "passive"))
    )
    (net (code "61") (name "EMMC_EN_N_1V8$1") (class "Default")
      (node (ref "X1") (pin "90") (pinfunction "1_90") (pintype "passive"))
    )
    (net (code "62") (name "EMMC_~{DISABLE$1}") (class "Default")
      (node (ref "R5") (pin "2") (pinfunction "2_2") (pintype "passive"))
      (node (ref "X1") (pin "2") (pinfunction "1_2") (pintype "passive"))
    )
    (net (code "63") (name "ETH_0_N") (class "Default")
      (node (ref "J1") (pin "10") (pinfunction "10_10") (pintype "passive"))
      (node (ref "X1") (pin "24") (pinfunction "1_24") (pintype "passive"))
    )
    (net (code "64") (name "ETH_0_P") (class "Default")
      (node (ref "J1") (pin "12") (pinfunction "12_12") (pintype "passive"))
      (node (ref "X1") (pin "22") (pinfunction "1_22") (pintype "passive"))
    )
    (net (code "65") (name "ETH_1_N") (class "Default")
      (node (ref "J1") (pin "6") (pinfunction "6_6") (pintype "passive"))
      (node (ref "X1") (pin "16") (pinfunction "1_16") (pintype "passive"))
    )
    (net (code "66") (name "ETH_1_P") (class "Default")
      (node (ref "J1") (pin "4") (pinfunction "4_4") (pintype "passive"))
      (node (ref "X1") (pin "18") (pinfunction "1_18") (pintype "passive"))
    )
    (net (code "67") (name "ETH_2_N") (class "Default")
      (node (ref "J1") (pin "9") (pinfunction "9_9") (pintype "passive"))
      (node (ref "X1") (pin "10") (pinfunction "1_10") (pintype "passive"))
    )
    (net (code "68") (name "ETH_2_P") (class "Default")
      (node (ref "J1") (pin "11") (pinfunction "11_11") (pintype "passive"))
      (node (ref "X1") (pin "12") (pinfunction "1_12") (pintype "passive"))
    )
    (net (code "69") (name "ETH_3_N") (class "Default")
      (node (ref "J1") (pin "5") (pinfunction "5_5") (pintype "passive"))
      (node (ref "X1") (pin "6") (pinfunction "1_6") (pintype "passive"))
    )
    (net (code "70") (name "ETH_3_P") (class "Default")
      (node (ref "J1") (pin "3") (pinfunction "3_3") (pintype "passive"))
      (node (ref "X1") (pin "4") (pinfunction "1_4") (pintype "passive"))
    )
    (net (code "71") (name "ETH_SYNC_IN") (class "Default")
      (node (ref "J1") (pin "16") (pinfunction "16_16") (pintype "passive"))
    )
    (net (code "72") (name "ETH_SYNC_OUT") (class "Default")
      (node (ref "J1") (pin "18") (pinfunction "18_18") (pintype "passive"))
    )
    (net (code "73") (name "ETH_~{GREEN}") (class "Default")
      (node (ref "J1") (pin "15") (pinfunction "15_15") (pintype "passive"))
      (node (ref "X1") (pin "166") (pinfunction "1_166") (pintype "passive"))
    )
    (net (code "74") (name "ETH_~{LED1}") (class "Default")
      (node (ref "J1") (pin "19") (pinfunction "19_19") (pintype "passive"))
    )
    (net (code "75") (name "ETH_~{YELLOW}") (class "Default")
      (node (ref "J1") (pin "17") (pinfunction "17_17") (pintype "passive"))
      (node (ref "X1") (pin "178") (pinfunction "1_178") (pintype "passive"))
    )
    (net (code "76") (name "GLOBAL_EN") (class "Default")
      (node (ref "J1") (pin "99") (pinfunction "99_99") (pintype "passive"))
    )
    (net (code "77") (name "GND") (class "Default")
      (node (ref "C1") (pin "2") (pinfunction "2_2") (pintype "passive"))
      (node (ref "C10") (pin "2") (pinfunction "2_2") (pintype "passive"))
      (node (ref "C177") (pin "2") (pinfunction "2_2") (pintype "passive"))
      (node (ref "C3") (pin "2") (pinfunction "2_2") (pintype "passive"))
      (node (ref "C56") (pin "2") (pinfunction "2_2") (pintype "passive"))
      (node (ref "C9") (pin "2") (pinfunction "2_2") (pintype "passive"))
      (node (ref "J1") (pin "1") (pinfunction "1_1") (pintype "passive"))
      (node (ref "J1") (pin "13") (pinfunction "13_13") (pintype "passive"))
      (node (ref "J1") (pin "14") (pinfunction "14_14") (pintype "passive"))
      (node (ref "J1") (pin "2") (pinfunction "2_2") (pintype "passive"))
      (node (ref "J1") (pin "22") (pinfunction "22_22") (pintype "passive"))
      (node (ref "J1") (pin "23") (pinfunction "23_23") (pintype "passive"))
      (node (ref "J1") (pin "32") (pinfunction "32_32") (pintype "passive"))
      (node (ref "J1") (pin "33") (pinfunction "33_33") (pintype "passive"))
      (node (ref "J1") (pin "42") (pinfunction "42_42") (pintype "passive"))
      (node (ref "J1") (pin "43") (pinfunction "43_43") (pintype "passive"))
      (node (ref "J1") (pin "52") (pinfunction "52_52") (pintype "passive"))
      (node (ref "J1") (pin "53") (pinfunction "53_53") (pintype "passive"))
      (node (ref "J1") (pin "59") (pinfunction "59_59") (pintype "passive"))
      (node (ref "J1") (pin "60") (pinfunction "60_60") (pintype "passive"))
      (node (ref "J1") (pin "65") (pinfunction "65_65") (pintype "passive"))
      (node (ref "J1") (pin "66") (pinfunction "66_66") (pintype "passive"))
      (node (ref "J1") (pin "7") (pinfunction "7_7") (pintype "passive"))
      (node (ref "J1") (pin "71") (pinfunction "71_71") (pintype "passive"))
      (node (ref "J1") (pin "74") (pinfunction "74_74") (pintype "passive"))
      (node (ref "J1") (pin "8") (pinfunction "8_8") (pintype "passive"))
      (node (ref "J1") (pin "98") (pinfunction "98_98") (pintype "passive"))
      (node (ref "J2") (pin "13") (pinfunction "13_13") (pintype "passive"))
      (node (ref "J2") (pin "14") (pinfunction "14_14") (pintype "passive"))
      (node (ref "J2") (pin "19") (pinfunction "19_19") (pintype "passive"))
      (node (ref "J2") (pin "20") (pinfunction "20_20") (pintype "passive"))
      (node (ref "J2") (pin "25") (pinfunction "25_25") (pintype "passive"))
      (node (ref "J2") (pin "26") (pinfunction "26_26") (pintype "passive"))
      (node (ref "J2") (pin "31") (pinfunction "31_31") (pintype "passive"))
      (node (ref "J2") (pin "32") (pinfunction "32_32") (pintype "passive"))
      (node (ref "J2") (pin "37") (pinfunction "37_37") (pintype "passive"))
      (node (ref "J2") (pin "38") (pinfunction "38_38") (pintype "passive"))
      (node (ref "J2") (pin "44") (pinfunction "44_44") (pintype "passive"))
      (node (ref "J2") (pin "50") (pinfunction "50_50") (pintype "passive"))
      (node (ref "J2") (pin "55") (pinfunction "55_55") (pintype "passive"))
      (node (ref "J2") (pin "56") (pinfunction "56_56") (pintype "passive"))
      (node (ref "J2") (pin "61") (pinfunction "61_61") (pintype "passive"))
      (node (ref "J2") (pin "62") (pinfunction "62_62") (pintype "passive"))
      (node (ref "J2") (pin "67") (pinfunction "67_67") (pintype "passive"))
      (node (ref "J2") (pin "68") (pinfunction "68_68") (pintype "passive"))
      (node (ref "J2") (pin "7") (pinfunction "7_7") (pintype "passive"))
      (node (ref "J2") (pin "73") (pinfunction "73_73") (pintype "passive"))
      (node (ref "J2") (pin "74") (pinfunction "74_74") (pintype "passive"))
      (node (ref "J2") (pin "79") (pinfunction "79_79") (pintype "passive"))
      (node (ref "J2") (pin "8") (pinfunction "8_8") (pintype "passive"))
      (node (ref "J2") (pin "80") (pinfunction "80_80") (pintype "passive"))
      (node (ref "J2") (pin "85") (pinfunction "85_85") (pintype "passive"))
      (node (ref "J2") (pin "86") (pinfunction "86_86") (pintype "passive"))
      (node (ref "J2") (pin "91") (pinfunction "91_91") (pintype "passive"))
      (node (ref "J2") (pin "92") (pinfunction "92_92") (pintype "passive"))
      (node (ref "J2") (pin "97") (pinfunction "97_97") (pintype "passive"))
      (node (ref "J2") (pin "98") (pinfunction "98_98") (pintype "passive"))
      (node (ref "MP1") (pin "1") (pinfunction "TP_1") (pintype "bidirectional"))
      (node (ref "MP2") (pin "1") (pinfunction "TP_1") (pintype "bidirectional"))
      (node (ref "MP3") (pin "1") (pinfunction "TP_1") (pintype "bidirectional"))
      (node (ref "MP4") (pin "1") (pinfunction "TP_1") (pintype "bidirectional"))
      (node (ref "Q2") (pin "2") (pinfunction "S_2") (pintype "passive"))
      (node (ref "R4") (pin "1") (pinfunction "1_1") (pintype "passive"))
      (node (ref "R6") (pin "1") (pinfunction "1_1") (pintype "passive"))
      (node (ref "R74") (pin "1") (pinfunction "1_1") (pintype "passive"))
      (node (ref "R77") (pin "1") (pinfunction "1_1") (pintype "passive"))
      (node (ref "R9") (pin "1") (pinfunction "1_1") (pintype "passive"))
      (node (ref "U1") (pin "25") (pinfunction "GND_25") (pintype "power_in"))
      (node (ref "U1") (pin "P9") (pinfunction "GND_P9") (pintype "power_in"))
      (node (ref "U7") (pin "3") (pinfunction "SGND_3") (pintype "power_in"))
      (node (ref "U7") (pin "5") (pinfunction "PGND_5") (pintype "power_in"))
      (node (ref "U7") (pin "6") (pinfunction "PGND_6") (pintype "power_in"))
      (node (ref "U7") (pin "P$1") (pinfunction "PGND_P$1") (pintype "power_in"))
      (node (ref "X1") (pin "1") (pinfunction "1_1") (pintype "passive"))
      (node (ref "X1") (pin "103") (pinfunction "1_103") (pintype "passive"))
      (node (ref "X1") (pin "104") (pinfunction "1_104") (pintype "passive"))
      (node (ref "X1") (pin "109") (pinfunction "1_109") (pintype "passive"))
      (node (ref "X1") (pin "110") (pinfunction "1_110") (pintype "passive"))
      (node (ref "X1") (pin "115") (pinfunction "1_115") (pintype "passive"))
      (node (ref "X1") (pin "116") (pinfunction "1_116") (pintype "passive"))
      (node (ref "X1") (pin "121") (pinfunction "1_121") (pintype "passive"))
      (node (ref "X1") (pin "122") (pinfunction "1_122") (pintype "passive"))
      (node (ref "X1") (pin "127") (pinfunction "1_127") (pintype "passive"))
      (node (ref "X1") (pin "128") (pinfunction "1_128") (pintype "passive"))
      (node (ref "X1") (pin "13") (pinfunction "1_13") (pintype "passive"))
      (node (ref "X1") (pin "133") (pinfunction "1_133") (pintype "passive"))
      (node (ref "X1") (pin "134") (pinfunction "1_134") (pintype "passive"))
      (node (ref "X1") (pin "139") (pinfunction "1_139") (pintype "passive"))
      (node (ref "X1") (pin "14") (pinfunction "1_14") (pintype "passive"))
      (node (ref "X1") (pin "140") (pinfunction "1_140") (pintype "passive"))
      (node (ref "X1") (pin "145") (pinfunction "1_145") (pintype "passive"))
      (node (ref "X1") (pin "146") (pinfunction "1_146") (pintype "passive"))
      (node (ref "X1") (pin "151") (pinfunction "1_151") (pintype "passive"))
      (node (ref "X1") (pin "152") (pinfunction "1_152") (pintype "passive"))
      (node (ref "X1") (pin "157") (pinfunction "1_157") (pintype "passive"))
      (node (ref "X1") (pin "158") (pinfunction "1_158") (pintype "passive"))
      (node (ref "X1") (pin "163") (pinfunction "1_163") (pintype "passive"))
      (node (ref "X1") (pin "164") (pinfunction "1_164") (pintype "passive"))
      (node (ref "X1") (pin "170") (pinfunction "1_170") (pintype "passive"))
      (node (ref "X1") (pin "181") (pinfunction "1_181") (pintype "passive"))
      (node (ref "X1") (pin "182") (pinfunction "1_182") (pintype "passive"))
      (node (ref "X1") (pin "187") (pinfunction "1_187") (pintype "passive"))
      (node (ref "X1") (pin "188") (pinfunction "1_188") (pintype "passive"))
      (node (ref "X1") (pin "19") (pinfunction "1_19") (pintype "passive"))
      (node (ref "X1") (pin "195") (pinfunction "1_195") (pintype "passive"))
      (node (ref "X1") (pin "196") (pinfunction "1_196") (pintype "passive"))
      (node (ref "X1") (pin "20") (pinfunction "1_20") (pintype "passive"))
      (node (ref "X1") (pin "25") (pinfunction "1_25") (pintype "passive"))
      (node (ref "X1") (pin "26") (pinfunction "1_26") (pintype "passive"))
      (node (ref "X1") (pin "31") (pinfunction "1_31") (pintype "passive"))
      (node (ref "X1") (pin "32") (pinfunction "1_32") (pintype "passive"))
      (node (ref "X1") (pin "37") (pinfunction "1_37") (pintype "passive"))
      (node (ref "X1") (pin "38") (pinfunction "1_38") (pintype "passive"))
      (node (ref "X1") (pin "43") (pinfunction "1_43") (pintype "passive"))
      (node (ref "X1") (pin "44") (pinfunction "1_44") (pintype "passive"))
      (node (ref "X1") (pin "49") (pinfunction "1_49") (pintype "passive"))
      (node (ref "X1") (pin "50") (pinfunction "1_50") (pintype "passive"))
      (node (ref "X1") (pin "55") (pinfunction "1_55") (pintype "passive"))
      (node (ref "X1") (pin "56") (pinfunction "1_56") (pintype "passive"))
      (node (ref "X1") (pin "61") (pinfunction "1_61") (pintype "passive"))
      (node (ref "X1") (pin "62") (pinfunction "1_62") (pintype "passive"))
      (node (ref "X1") (pin "67") (pinfunction "1_67") (pintype "passive"))
      (node (ref "X1") (pin "68") (pinfunction "1_68") (pintype "passive"))
      (node (ref "X1") (pin "7") (pinfunction "1_7") (pintype "passive"))
      (node (ref "X1") (pin "73") (pinfunction "1_73") (pintype "passive"))
      (node (ref "X1") (pin "74") (pinfunction "1_74") (pintype "passive"))
      (node (ref "X1") (pin "79") (pinfunction "1_79") (pintype "passive"))
      (node (ref "X1") (pin "8") (pinfunction "1_8") (pintype "passive"))
      (node (ref "X1") (pin "80") (pinfunction "1_80") (pintype "passive"))
      (node (ref "X1") (pin "85") (pinfunction "1_85") (pintype "passive"))
      (node (ref "X1") (pin "86") (pinfunction "1_86") (pintype "passive"))
      (node (ref "X1") (pin "91") (pinfunction "1_91") (pintype "passive"))
      (node (ref "X1") (pin "92") (pinfunction "1_92") (pintype "passive"))
      (node (ref "X1") (pin "97") (pinfunction "1_97") (pintype "passive"))
      (node (ref "X1") (pin "98") (pinfunction "1_98") (pintype "passive"))
    )
    (net (code "78") (name "GPIO0$1") (class "Default")
      (node (ref "J1") (pin "36") (pinfunction "36_36") (pintype "passive"))
      (node (ref "X1") (pin "3") (pinfunction "1_3") (pintype "passive"))
    )
    (net (code "79") (name "GPIO0-27_VDD$1") (class "Default")
      (node (ref "X1") (pin "39") (pinfunction "1_39") (pintype "passive"))
      (node (ref "X1") (pin "40") (pinfunction "1_40") (pintype "passive"))
    )
    (net (code "80") (name "GPIO1$1") (class "Default")
      (node (ref "J1") (pin "35") (pinfunction "35_35") (pintype "passive"))
      (node (ref "X1") (pin "5") (pinfunction "1_5") (pintype "passive"))
    )
    (net (code "81") (name "GPIO2$1") (class "Default")
      (node (ref "J1") (pin "58") (pinfunction "58_58") (pintype "passive"))
      (node (ref "R7") (pin "1") (pinfunction "1_1") (pintype "passive"))
      (node (ref "U1") (pin "P20") (pinfunction "SDA_P20") (pintype "bidirectional"))
      (node (ref "X1") (pin "9") (pinfunction "1_9") (pintype "passive"))
    )
    (net (code "82") (name "GPIO3$1") (class "Default")
      (node (ref "J1") (pin "56") (pinfunction "56_56") (pintype "passive"))
      (node (ref "R8") (pin "1") (pinfunction "1_1") (pintype "passive"))
      (node (ref "U1") (pin "P19") (pinfunction "SCL_P19") (pintype "bidirectional"))
      (node (ref "X1") (pin "11") (pinfunction "1_11") (pintype "passive"))
    )
    (net (code "83") (name "GPIO4$1") (class "Default")
      (node (ref "J1") (pin "54") (pinfunction "54_54") (pintype "passive"))
      (node (ref "X1") (pin "15") (pinfunction "1_15") (pintype "passive"))
    )
    (net (code "84") (name "GPIO5$1") (class "Default")
      (node (ref "J1") (pin "34") (pinfunction "34_34") (pintype "passive"))
      (node (ref "X1") (pin "17") (pinfunction "1_17") (pintype "passive"))
    )
    (net (code "85") (name "GPIO6$1") (class "Default")
      (node (ref "J1") (pin "30") (pinfunction "30_30") (pintype "passive"))
      (node (ref "X1") (pin "21") (pinfunction "1_21") (pintype "passive"))
    )
    (net (code "86") (name "GPIO7$1") (class "Default")
      (node (ref "J1") (pin "37") (pinfunction "37_37") (pintype "passive"))
      (node (ref "X1") (pin "23") (pinfunction "1_23") (pintype "passive"))
    )
    (net (code "87") (name "GPIO8$1") (class "Default")
      (node (ref "J1") (pin "39") (pinfunction "39_39") (pintype "passive"))
      (node (ref "X1") (pin "27") (pinfunction "1_27") (pintype "passive"))
    )
    (net (code "88") (name "GPIO9$1") (class "Default")
      (node (ref "J1") (pin "40") (pinfunction "40_40") (pintype "passive"))
      (node (ref "X1") (pin "29") (pinfunction "1_29") (pintype "passive"))
    )
    (net (code "89") (name "GPIO10$1") (class "Default")
      (node (ref "J1") (pin "44") (pinfunction "44_44") (pintype "passive"))
      (node (ref "X1") (pin "33") (pinfunction "1_33") (pintype "passive"))
    )
    (net (code "90") (name "GPIO11$1") (class "Default")
      (node (ref "J1") (pin "38") (pinfunction "38_38") (pintype "passive"))
      (node (ref "X1") (pin "35") (pinfunction "1_35") (pintype "passive"))
    )
    (net (code "91") (name "GPIO12$1") (class "Default")
      (node (ref "J1") (pin "31") (pinfunction "31_31") (pintype "passive"))
      (node (ref "X1") (pin "45") (pinfunction "1_45") (pintype "passive"))
    )
    (net (code "92") (name "GPIO13$1") (class "Default")
      (node (ref "J1") (pin "28") (pinfunction "28_28") (pintype "passive"))
      (node (ref "X1") (pin "47") (pinfunction "1_47") (pintype "passive"))
    )
    (net (code "93") (name "GPIO14$1") (class "Default")
      (node (ref "J1") (pin "55") (pinfunction "55_55") (pintype "passive"))
      (node (ref "X1") (pin "51") (pinfunction "1_51") (pintype "passive"))
    )
    (net (code "94") (name "GPIO15$1") (class "Default")
      (node (ref "J1") (pin "51") (pinfunction "51_51") (pintype "passive"))
      (node (ref "X1") (pin "53") (pinfunction "1_53") (pintype "passive"))
    )
    (net (code "95") (name "GPIO16$1") (class "Default")
      (node (ref "J1") (pin "29") (pinfunction "29_29") (pintype "passive"))
      (node (ref "X1") (pin "57") (pinfunction "1_57") (pintype "passive"))
    )
    (net (code "96") (name "GPIO17$1") (class "Default")
      (node (ref "J1") (pin "50") (pinfunction "50_50") (pintype "passive"))
      (node (ref "X1") (pin "59") (pinfunction "1_59") (pintype "passive"))
    )
    (net (code "97") (name "GPIO18$1") (class "Default")
      (node (ref "J1") (pin "49") (pinfunction "49_49") (pintype "passive"))
      (node (ref "X1") (pin "63") (pinfunction "1_63") (pintype "passive"))
    )
    (net (code "98") (name "GPIO19$1") (class "Default")
      (node (ref "J1") (pin "26") (pinfunction "26_26") (pintype "passive"))
      (node (ref "X1") (pin "65") (pinfunction "1_65") (pintype "passive"))
    )
    (net (code "99") (name "GPIO20$1") (class "Default")
      (node (ref "J1") (pin "27") (pinfunction "27_27") (pintype "passive"))
      (node (ref "X1") (pin "69") (pinfunction "1_69") (pintype "passive"))
    )
    (net (code "100") (name "GPIO21$1") (class "Default")
      (node (ref "J1") (pin "25") (pinfunction "25_25") (pintype "passive"))
      (node (ref "X1") (pin "71") (pinfunction "1_71") (pintype "passive"))
    )
    (net (code "101") (name "GPIO22$1") (class "Default")
      (node (ref "J1") (pin "46") (pinfunction "46_46") (pintype "passive"))
      (node (ref "X1") (pin "75") (pinfunction "1_75") (pintype "passive"))
    )
    (net (code "102") (name "GPIO23$1") (class "Default")
      (node (ref "J1") (pin "47") (pinfunction "47_47") (pintype "passive"))
      (node (ref "X1") (pin "77") (pinfunction "1_77") (pintype "passive"))
    )
    (net (code "103") (name "GPIO24$1") (class "Default")
      (node (ref "J1") (pin "45") (pinfunction "45_45") (pintype "passive"))
      (node (ref "X1") (pin "81") (pinfunction "1_81") (pintype "passive"))
    )
    (net (code "104") (name "GPIO25$1") (class "Default")
      (node (ref "J1") (pin "41") (pinfunction "41_41") (pintype "passive"))
      (node (ref "X1") (pin "83") (pinfunction "1_83") (pintype "passive"))
    )
    (net (code "105") (name "GPIO26$1") (class "Default")
      (node (ref "J1") (pin "24") (pinfunction "24_24") (pintype "passive"))
      (node (ref "X1") (pin "87") (pinfunction "1_87") (pintype "passive"))
    )
    (net (code "106") (name "GPIO27$1") (class "Default")
      (node (ref "J1") (pin "48") (pinfunction "48_48") (pintype "passive"))
      (node (ref "X1") (pin "89") (pinfunction "1_89") (pintype "passive"))
    )
    (net (code "107") (name "GPIO28$1") (class "Default")
      (node (ref "U1") (pin "P1") (pinfunction "P00_P1") (pintype "bidirectional"))
      (node (ref "X1") (pin "28") (pinfunction "1_28") (pintype "passive"))
    )
    (net (code "108") (name "GPIO28-45_VDD$1") (class "Default")
      (node (ref "X1") (pin "41") (pinfunction "1_41") (pintype "passive"))
      (node (ref "X1") (pin "42") (pinfunction "1_42") (pintype "passive"))
    )
    (net (code "109") (name "GPIO29$1") (class "Default")
      (node (ref "U1") (pin "P2") (pinfunction "P01_P2") (pintype "bidirectional"))
      (node (ref "X1") (pin "30") (pinfunction "1_30") (pintype "passive"))
    )
    (net (code "110") (name "GPIO30$1") (class "Default")
      (node (ref "U1") (pin "P3") (pinfunction "P02_P3") (pintype "bidirectional"))
      (node (ref "X1") (pin "34") (pinfunction "1_34") (pintype "passive"))
    )
    (net (code "111") (name "GPIO31$1") (class "Default")
      (node (ref "U1") (pin "P4") (pinfunction "P03_P4") (pintype "bidirectional"))
      (node (ref "X1") (pin "36") (pinfunction "1_36") (pintype "passive"))
    )
    (net (code "112") (name "GPIO32$1") (class "Default")
      (node (ref "U1") (pin "P5") (pinfunction "P04_P5") (pintype "bidirectional"))
      (node (ref "X1") (pin "46") (pinfunction "1_46") (pintype "passive"))
    )
    (net (code "113") (name "GPIO33$1") (class "Default")
      (node (ref "U1") (pin "P6") (pinfunction "P05_P6") (pintype "bidirectional"))
      (node (ref "X1") (pin "48") (pinfunction "1_48") (pintype "passive"))
    )
    (net (code "114") (name "GPIO34$1") (class "Default")
      (node (ref "U1") (pin "P7") (pinfunction "P06_P7") (pintype "bidirectional"))
      (node (ref "X1") (pin "52") (pinfunction "1_52") (pintype "passive"))
    )
    (net (code "115") (name "GPIO35$1") (class "Default")
      (node (ref "U1") (pin "P8") (pinfunction "P07_P8") (pintype "bidirectional"))
      (node (ref "X1") (pin "54") (pinfunction "1_54") (pintype "passive"))
    )
    (net (code "116") (name "GPIO36$1") (class "Default")
      (node (ref "U1") (pin "P10") (pinfunction "P10_P10") (pintype "bidirectional"))
      (node (ref "X1") (pin "58") (pinfunction "1_58") (pintype "passive"))
    )
    (net (code "117") (name "GPIO37$1") (class "Default")
      (node (ref "U1") (pin "P11") (pinfunction "P11_P11") (pintype "bidirectional"))
      (node (ref "X1") (pin "60") (pinfunction "1_60") (pintype "passive"))
    )
    (net (code "118") (name "GPIO38$1") (class "Default")
      (node (ref "U1") (pin "P12") (pinfunction "P12_P12") (pintype "bidirectional"))
      (node (ref "X1") (pin "64") (pinfunction "1_64") (pintype "passive"))
    )
    (net (code "119") (name "GPIO39$1") (class "Default")
      (node (ref "U1") (pin "P13") (pinfunction "P13_P13") (pintype "bidirectional"))
      (node (ref "X1") (pin "66") (pinfunction "1_66") (pintype "passive"))
    )
    (net (code "120") (name "GPIO40$1") (class "Default")
      (node (ref "U1") (pin "P14") (pinfunction "P14_P14") (pintype "bidirectional"))
      (node (ref "X1") (pin "70") (pinfunction "1_70") (pintype "passive"))
    )
    (net (code "121") (name "GPIO41$1") (class "Default")
      (node (ref "U1") (pin "P15") (pinfunction "P15_P15") (pintype "bidirectional"))
      (node (ref "X1") (pin "72") (pinfunction "1_72") (pintype "passive"))
    )
    (net (code "122") (name "GPIO42$1") (class "Default")
      (node (ref "U1") (pin "P16") (pinfunction "P16_P16") (pintype "bidirectional"))
      (node (ref "X1") (pin "76") (pinfunction "1_76") (pintype "passive"))
    )
    (net (code "123") (name "GPIO43$1") (class "Default")
      (node (ref "U1") (pin "P17") (pinfunction "P17_P17") (pintype "bidirectional"))
      (node (ref "X1") (pin "78") (pinfunction "1_78") (pintype "passive"))
    )
    (net (code "124") (name "GPIO_INT") (class "Default")
      (node (ref "R2") (pin "1") (pinfunction "1_1") (pintype "passive"))
      (node (ref "U1") (pin "P22") (pinfunction "~{INT}_P22") (pintype "bidirectional"))
    )
    (net (code "125") (name "GPIO_VREF$2") (class "Default")
      (node (ref "J1") (pin "78") (pinfunction "78_78") (pintype "passive"))
      (node (ref "R79") (pin "2") (pinfunction "2_2") (pintype "passive"))
    )
    (net (code "126") (name "GPIO_~{RESET}") (class "Default")
      (node (ref "R1") (pin "1") (pinfunction "1_1") (pintype "passive"))
      (node (ref "U1") (pin "P24") (pinfunction "~{RESET}_P24") (pintype "bidirectional"))
    )
    (net (code "127") (name "HDMI1_CEC") (class "Default")
      (node (ref "J2") (pin "49") (pinfunction "49_49") (pintype "passive"))
    )
    (net (code "128") (name "HDMI1_CLK_N") (class "Default")
      (node (ref "J2") (pin "66") (pinfunction "66_66") (pintype "passive"))
    )
    (net (code "129") (name "HDMI1_CLK_P") (class "Default")
      (node (ref "J2") (pin "64") (pinfunction "64_64") (pintype "passive"))
    )
    (net (code "130") (name "HDMI1_HPG") (class "Default")
      (node (ref "J2") (pin "43") (pinfunction "43_43") (pintype "passive"))
    )
    (net (code "131") (name "HDMI1_SCL") (class "Default")
      (node (ref "J2") (pin "47") (pinfunction "47_47") (pintype "passive"))
    )
    (net (code "132") (name "HDMI1_SDA") (class "Default")
      (node (ref "J2") (pin "45") (pinfunction "45_45") (pintype "passive"))
    )
    (net (code "133") (name "HDMI1_TX0_N") (class "Default")
      (node (ref "J2") (pin "60") (pinfunction "60_60") (pintype "passive"))
    )
    (net (code "134") (name "HDMI1_TX0_P") (class "Default")
      (node (ref "J2") (pin "58") (pinfunction "58_58") (pintype "passive"))
    )
    (net (code "135") (name "HDMI1_TX1_N") (class "Default")
      (node (ref "J2") (pin "54") (pinfunction "54_54") (pintype "passive"))
    )
    (net (code "136") (name "HDMI1_TX1_P") (class "Default")
      (node (ref "J2") (pin "52") (pinfunction "52_52") (pintype "passive"))
    )
    (net (code "137") (name "HDMI1_TX2_N") (class "Default")
      (node (ref "J2") (pin "48") (pinfunction "48_48") (pintype "passive"))
    )
    (net (code "138") (name "HDMI1_TX2_P") (class "Default")
      (node (ref "J2") (pin "46") (pinfunction "46_46") (pintype "passive"))
    )
    (net (code "139") (name "HDMI_HPD_N_1V8$1") (class "Default")
      (node (ref "Q2") (pin "1") (pinfunction "G_1") (pintype "passive"))
      (node (ref "X1") (pin "88") (pinfunction "1_88") (pintype "passive"))
    )
    (net (code "140") (name "Net-(C58-Pad2)") (class "Default")
      (node (ref "C58") (pin "2") (pinfunction "2_2") (pintype "passive"))
      (node (ref "R76") (pin "2") (pinfunction "2_2") (pintype "passive"))
    )
    (net (code "141") (name "Net-(C60-Pad1)") (class "Default")
      (node (ref "C60") (pin "1") (pinfunction "1_1") (pintype "passive"))
      (node (ref "R78") (pin "1") (pinfunction "1_1") (pintype "passive"))
    )
    (net (code "142") (name "Net-(U7-BURST)") (class "Default")
      (node (ref "C10") (pin "1") (pinfunction "1_1") (pintype "passive"))
      (node (ref "R74") (pin "2") (pinfunction "2_2") (pintype "passive"))
      (node (ref "U7") (pin "2") (pinfunction "BURST_2") (pintype "input"))
    )
    (net (code "143") (name "Net-(U7-FB)") (class "Default")
      (node (ref "C55") (pin "2") (pinfunction "2_2") (pintype "passive"))
      (node (ref "C60") (pin "2") (pinfunction "2_2") (pintype "passive"))
      (node (ref "R75") (pin "1") (pinfunction "1_1") (pintype "passive"))
      (node (ref "R76") (pin "1") (pinfunction "1_1") (pintype "passive"))
      (node (ref "R77") (pin "2") (pinfunction "2_2") (pintype "passive"))
      (node (ref "U7") (pin "13") (pinfunction "FB_13") (pintype "output"))
    )
    (net (code "144") (name "Net-(U7-RT)") (class "Default")
      (node (ref "R6") (pin "2") (pinfunction "2_2") (pintype "passive"))
      (node (ref "U7") (pin "1") (pinfunction "RT_1") (pintype "input"))
    )
    (net (code "145") (name "Net-(U7-SW1)") (class "Default")
      (node (ref "L4") (pin "1") (pinfunction "1_1") (pintype "passive"))
      (node (ref "U7") (pin "4") (pinfunction "SW1_4") (pintype "input"))
    )
    (net (code "146") (name "Net-(U7-SW2)") (class "Default")
      (node (ref "D2") (pin "A") (pinfunction "A_A") (pintype "passive"))
      (node (ref "L4") (pin "2") (pinfunction "2_2") (pintype "passive"))
      (node (ref "U7") (pin "7") (pinfunction "SW2_7") (pintype "input"))
    )
    (net (code "147") (name "Net-(U7-VC)") (class "Default")
      (node (ref "C55") (pin "1") (pinfunction "1_1") (pintype "passive"))
      (node (ref "R78") (pin "2") (pinfunction "2_2") (pintype "passive"))
      (node (ref "U7") (pin "14") (pinfunction "VC_14") (pintype "input"))
    )
    (net (code "148") (name "PCIE_CLK_N") (class "Default")
      (node (ref "J2") (pin "12") (pinfunction "12_12") (pintype "passive"))
      (node (ref "X1") (pin "132") (pinfunction "1_132") (pintype "passive"))
    )
    (net (code "149") (name "PCIE_CLK_P") (class "Default")
      (node (ref "J2") (pin "10") (pinfunction "10_10") (pintype "passive"))
      (node (ref "X1") (pin "130") (pinfunction "1_130") (pintype "passive"))
    )
    (net (code "150") (name "PCIE_RX_N") (class "Default")
      (node (ref "J2") (pin "18") (pinfunction "18_18") (pintype "passive"))
      (node (ref "X1") (pin "156") (pinfunction "1_156") (pintype "passive"))
    )
    (net (code "151") (name "PCIE_RX_P") (class "Default")
      (node (ref "J2") (pin "16") (pinfunction "16_16") (pintype "passive"))
      (node (ref "X1") (pin "154") (pinfunction "1_154") (pintype "passive"))
    )
    (net (code "152") (name "PCIE_TX_N") (class "Default")
      (node (ref "J2") (pin "24") (pinfunction "24_24") (pintype "passive"))
      (node (ref "X1") (pin "162") (pinfunction "1_162") (pintype "passive"))
    )
    (net (code "153") (name "PCIE_TX_P") (class "Default")
      (node (ref "J2") (pin "22") (pinfunction "22_22") (pintype "passive"))
      (node (ref "X1") (pin "160") (pinfunction "1_160") (pintype "passive"))
    )
    (net (code "154") (name "PCIE_~{CLKREQ}") (class "Default")
      (node (ref "J2") (pin "2") (pinfunction "2_2") (pintype "passive"))
      (node (ref "X1") (pin "124") (pinfunction "1_124") (pintype "passive"))
    )
    (net (code "155") (name "PCIE_~{RST}") (class "Default")
      (node (ref "J2") (pin "9") (pinfunction "9_9") (pintype "passive"))
      (node (ref "X1") (pin "126") (pinfunction "1_126") (pintype "passive"))
    )
    (net (code "156") (name "PI_LED_~{PWR}") (class "Default")
      (node (ref "J1") (pin "95") (pinfunction "95_95") (pintype "passive"))
    )
    (net (code "157") (name "PI_~{LED_ACT}") (class "Default")
      (node (ref "J1") (pin "21") (pinfunction "21_21") (pintype "passive"))
    )
    (net (code "158") (name "RUN_PG") (class "Default")
      (node (ref "J1") (pin "92") (pinfunction "92_92") (pintype "passive"))
      (node (ref "R11") (pin "2") (pinfunction "2_2") (pintype "passive"))
    )
    (net (code "159") (name "RUN__PG") (class "Default")
      (node (ref "R11") (pin "1") (pinfunction "1_1") (pintype "passive"))
      (node (ref "X1") (pin "177") (pinfunction "1_177") (pintype "passive"))
    )
    (net (code "160") (name "SD_CLK") (class "Default")
      (node (ref "J1") (pin "57") (pinfunction "57_57") (pintype "passive"))
    )
    (net (code "161") (name "SD_CMD") (class "Default")
      (node (ref "J1") (pin "62") (pinfunction "62_62") (pintype "passive"))
    )
    (net (code "162") (name "SD_DAT0") (class "Default")
      (node (ref "J1") (pin "63") (pinfunction "63_63") (pintype "passive"))
    )
    (net (code "163") (name "SD_DAT1") (class "Default")
      (node (ref "J1") (pin "67") (pinfunction "67_67") (pintype "passive"))
    )
    (net (code "164") (name "SD_DAT2") (class "Default")
      (node (ref "J1") (pin "69") (pinfunction "69_69") (pintype "passive"))
    )
    (net (code "165") (name "SD_DAT3") (class "Default")
      (node (ref "J1") (pin "61") (pinfunction "61_61") (pintype "passive"))
    )
    (net (code "166") (name "SD_DAT4") (class "Default")
      (node (ref "J1") (pin "68") (pinfunction "68_68") (pintype "passive"))
    )
    (net (code "167") (name "SD_DAT5") (class "Default")
      (node (ref "J1") (pin "64") (pinfunction "64_64") (pintype "passive"))
    )
    (net (code "168") (name "SD_DAT6") (class "Default")
      (node (ref "J1") (pin "72") (pinfunction "72_72") (pintype "passive"))
    )
    (net (code "169") (name "SD_DAT7") (class "Default")
      (node (ref "J1") (pin "70") (pinfunction "70_70") (pintype "passive"))
    )
    (net (code "170") (name "SD_PWR_ON") (class "Default")
      (node (ref "J1") (pin "75") (pinfunction "75_75") (pintype "passive"))
    )
    (net (code "171") (name "SD_VDD_OV") (class "Default")
      (node (ref "J1") (pin "73") (pinfunction "73_73") (pintype "passive"))
    )
    (net (code "172") (name "VDAC$1") (class "Default")
      (node (ref "X1") (pin "189") (pinfunction "1_189") (pintype "passive"))
      (node (ref "X1") (pin "190") (pinfunction "1_190") (pintype "passive"))
    )
    (net (code "173") (name "VDAC_COMP") (class "Default")
      (node (ref "J2") (pin "11") (pinfunction "11_11") (pintype "passive"))
    )
    (net (code "174") (name "VDD_CORE$1") (class "Default")
      (node (ref "X1") (pin "179") (pinfunction "1_179") (pintype "passive"))
    )
    (net (code "175") (name "unconnected-(J1-Pad76)") (class "Default")
      (node (ref "J1") (pin "76") (pinfunction "76_76") (pintype "passive"))
    )
    (net (code "176") (name "unconnected-(J1-Pad89)") (class "Default")
      (node (ref "J1") (pin "89") (pinfunction "89_89") (pintype "passive"))
    )
    (net (code "177") (name "unconnected-(J1-Pad91)") (class "Default")
      (node (ref "J1") (pin "91") (pinfunction "91_91") (pintype "passive"))
    )
    (net (code "178") (name "unconnected-(J1-Pad97)") (class "Default")
      (node (ref "J1") (pin "97") (pinfunction "97_97") (pintype "passive"))
    )
    (net (code "179") (name "unconnected-(J2-Pad4)") (class "Default")
      (node (ref "J2") (pin "4") (pinfunction "4_4") (pintype "passive"))
    )
    (net (code "180") (name "unconnected-(J2-Pad6)") (class "Default")
      (node (ref "J2") (pin "6") (pinfunction "6_6") (pintype "passive"))
    )
    (net (code "181") (name "unconnected-(X1CD-1-Pad172)") (class "Default")
      (node (ref "X1") (pin "172") (pinfunction "1_172") (pintype "passive"))
    )
    (net (code "182") (name "unconnected-(X1CF-1-Pad174)") (class "Default")
      (node (ref "X1") (pin "174") (pinfunction "1_174") (pintype "passive"))
    )
    (net (code "183") (name "unconnected-(X1CH-1-Pad176)") (class "Default")
      (node (ref "X1") (pin "176") (pinfunction "1_176") (pintype "passive"))
    )
    (net (code "184") (name "unconnected-(X1CM-1-Pad180)") (class "Default")
      (node (ref "X1") (pin "180") (pinfunction "1_180") (pintype "passive"))
    )
    (net (code "185") (name "~{RPIBOOT$2}") (class "Default")
      (node (ref "J1") (pin "93") (pinfunction "93_93") (pintype "passive"))
      (node (ref "R5") (pin "1") (pinfunction "1_1") (pintype "passive"))
    )
  )
)
